# INV_OG5K_PW_V1.net
KiCad netlist of a schematic drawn in Altium Designer
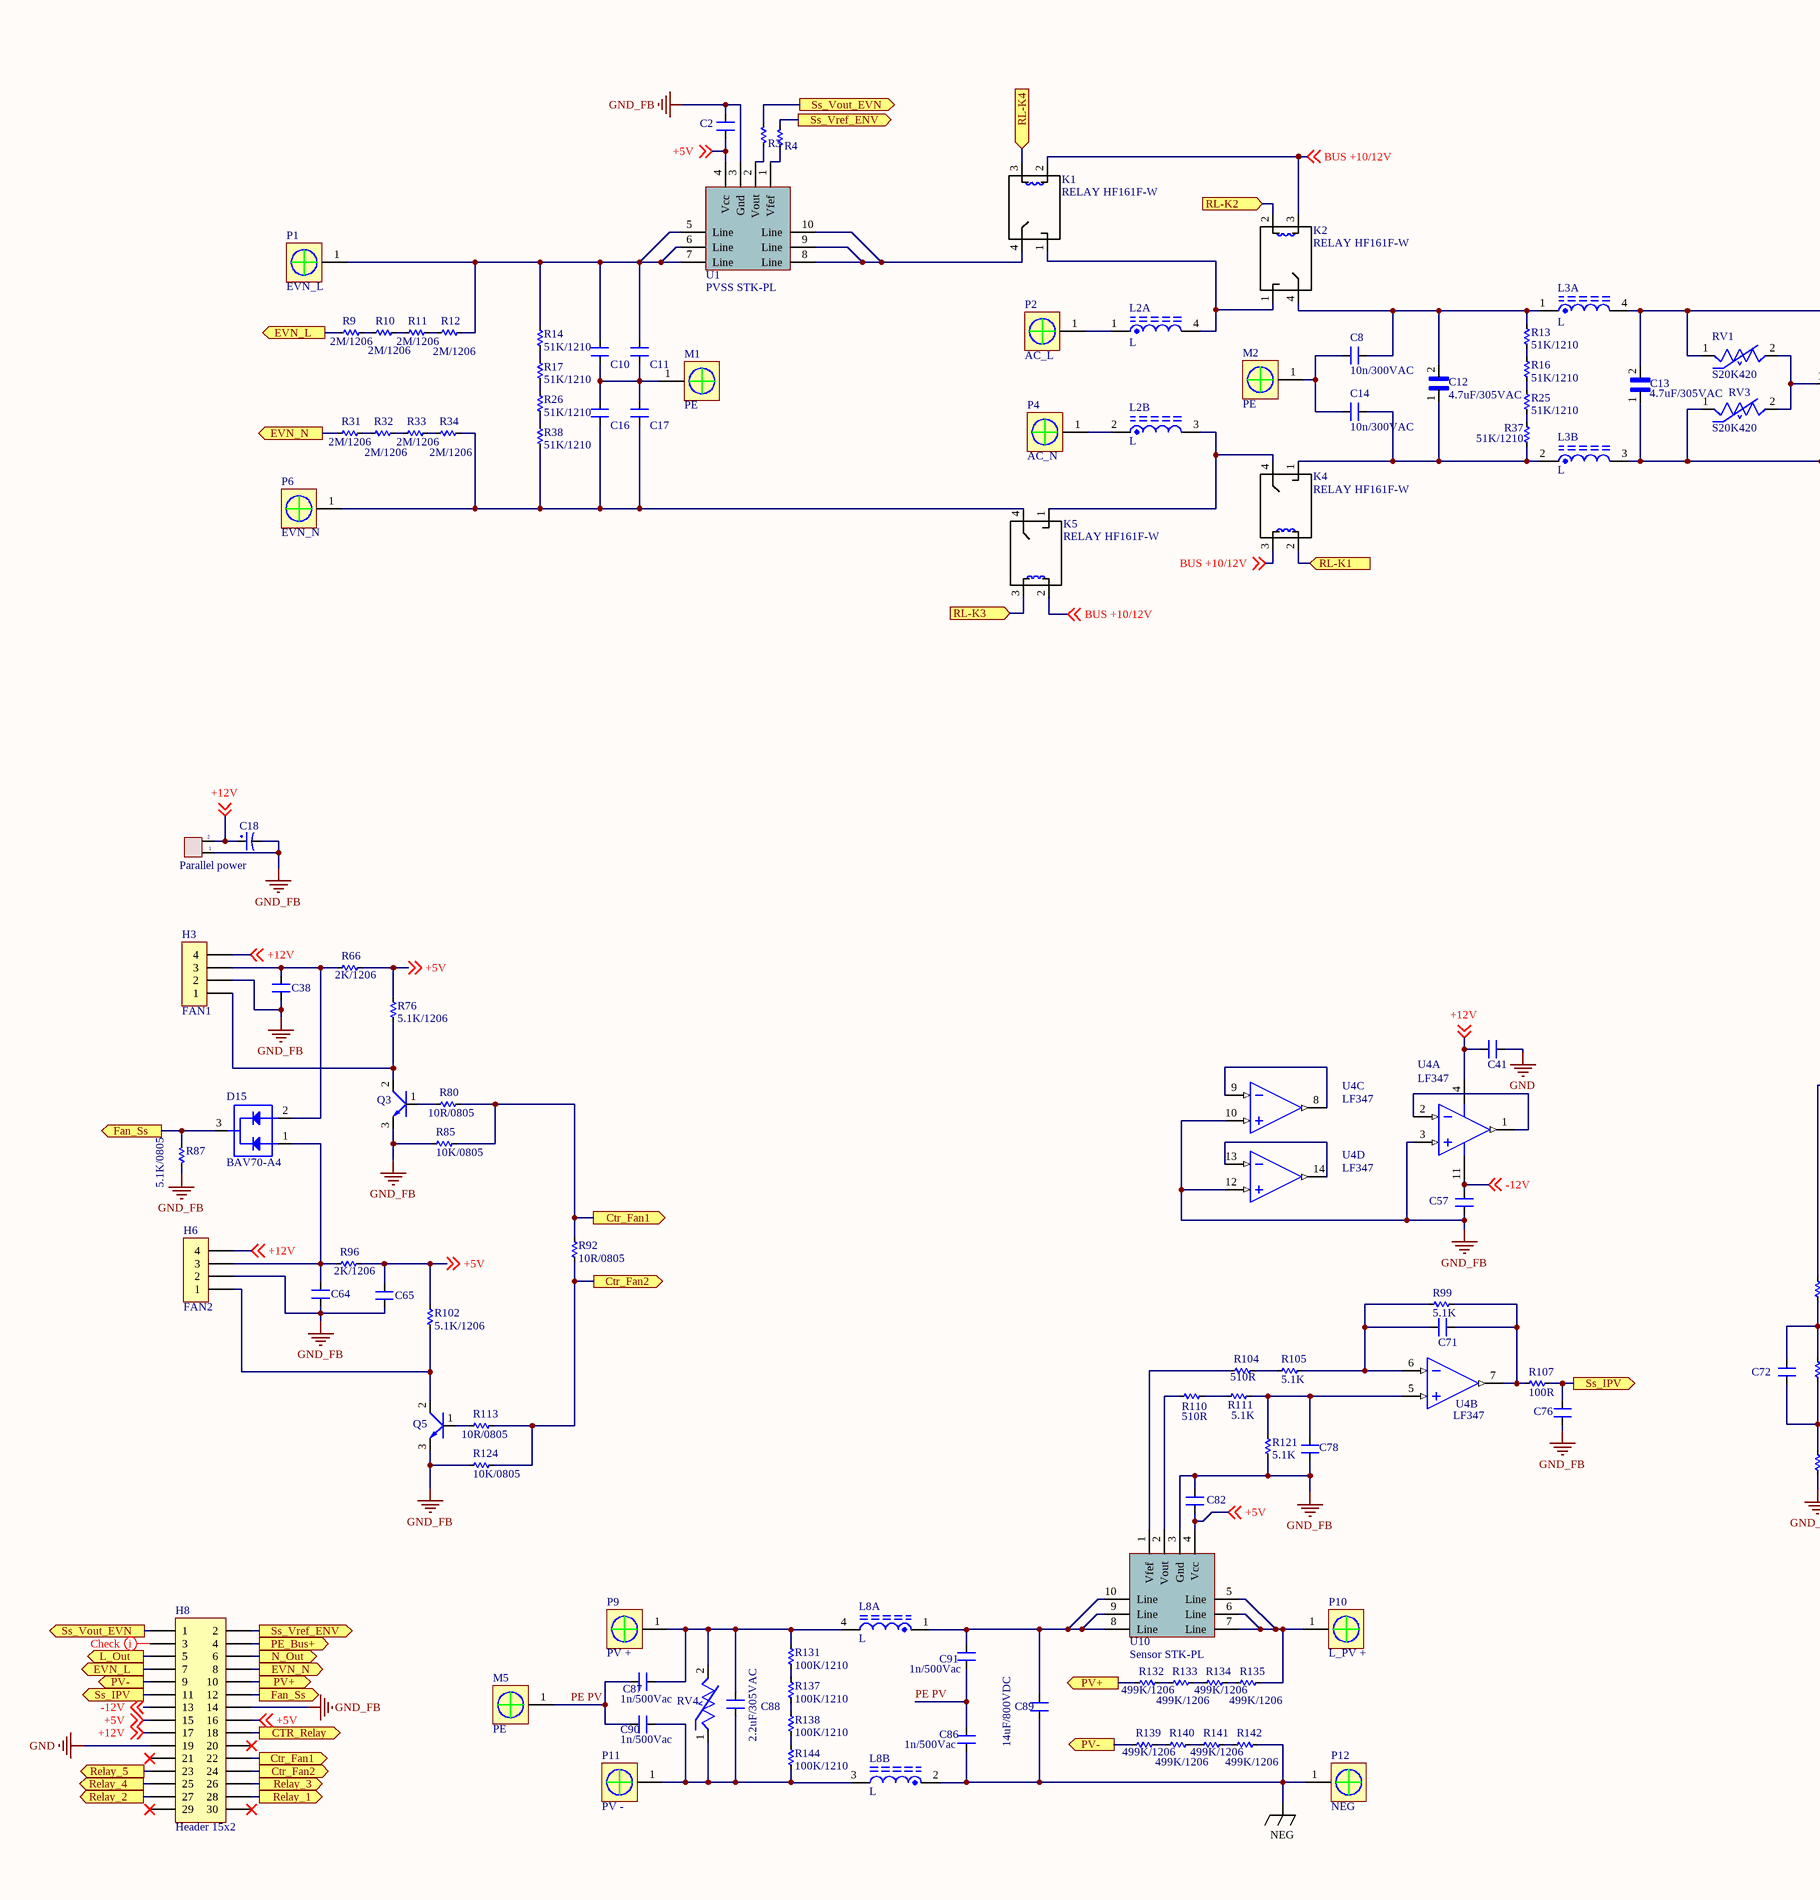
[diagram p0: INV.OG5K.PW.V1.SchDoc, left]
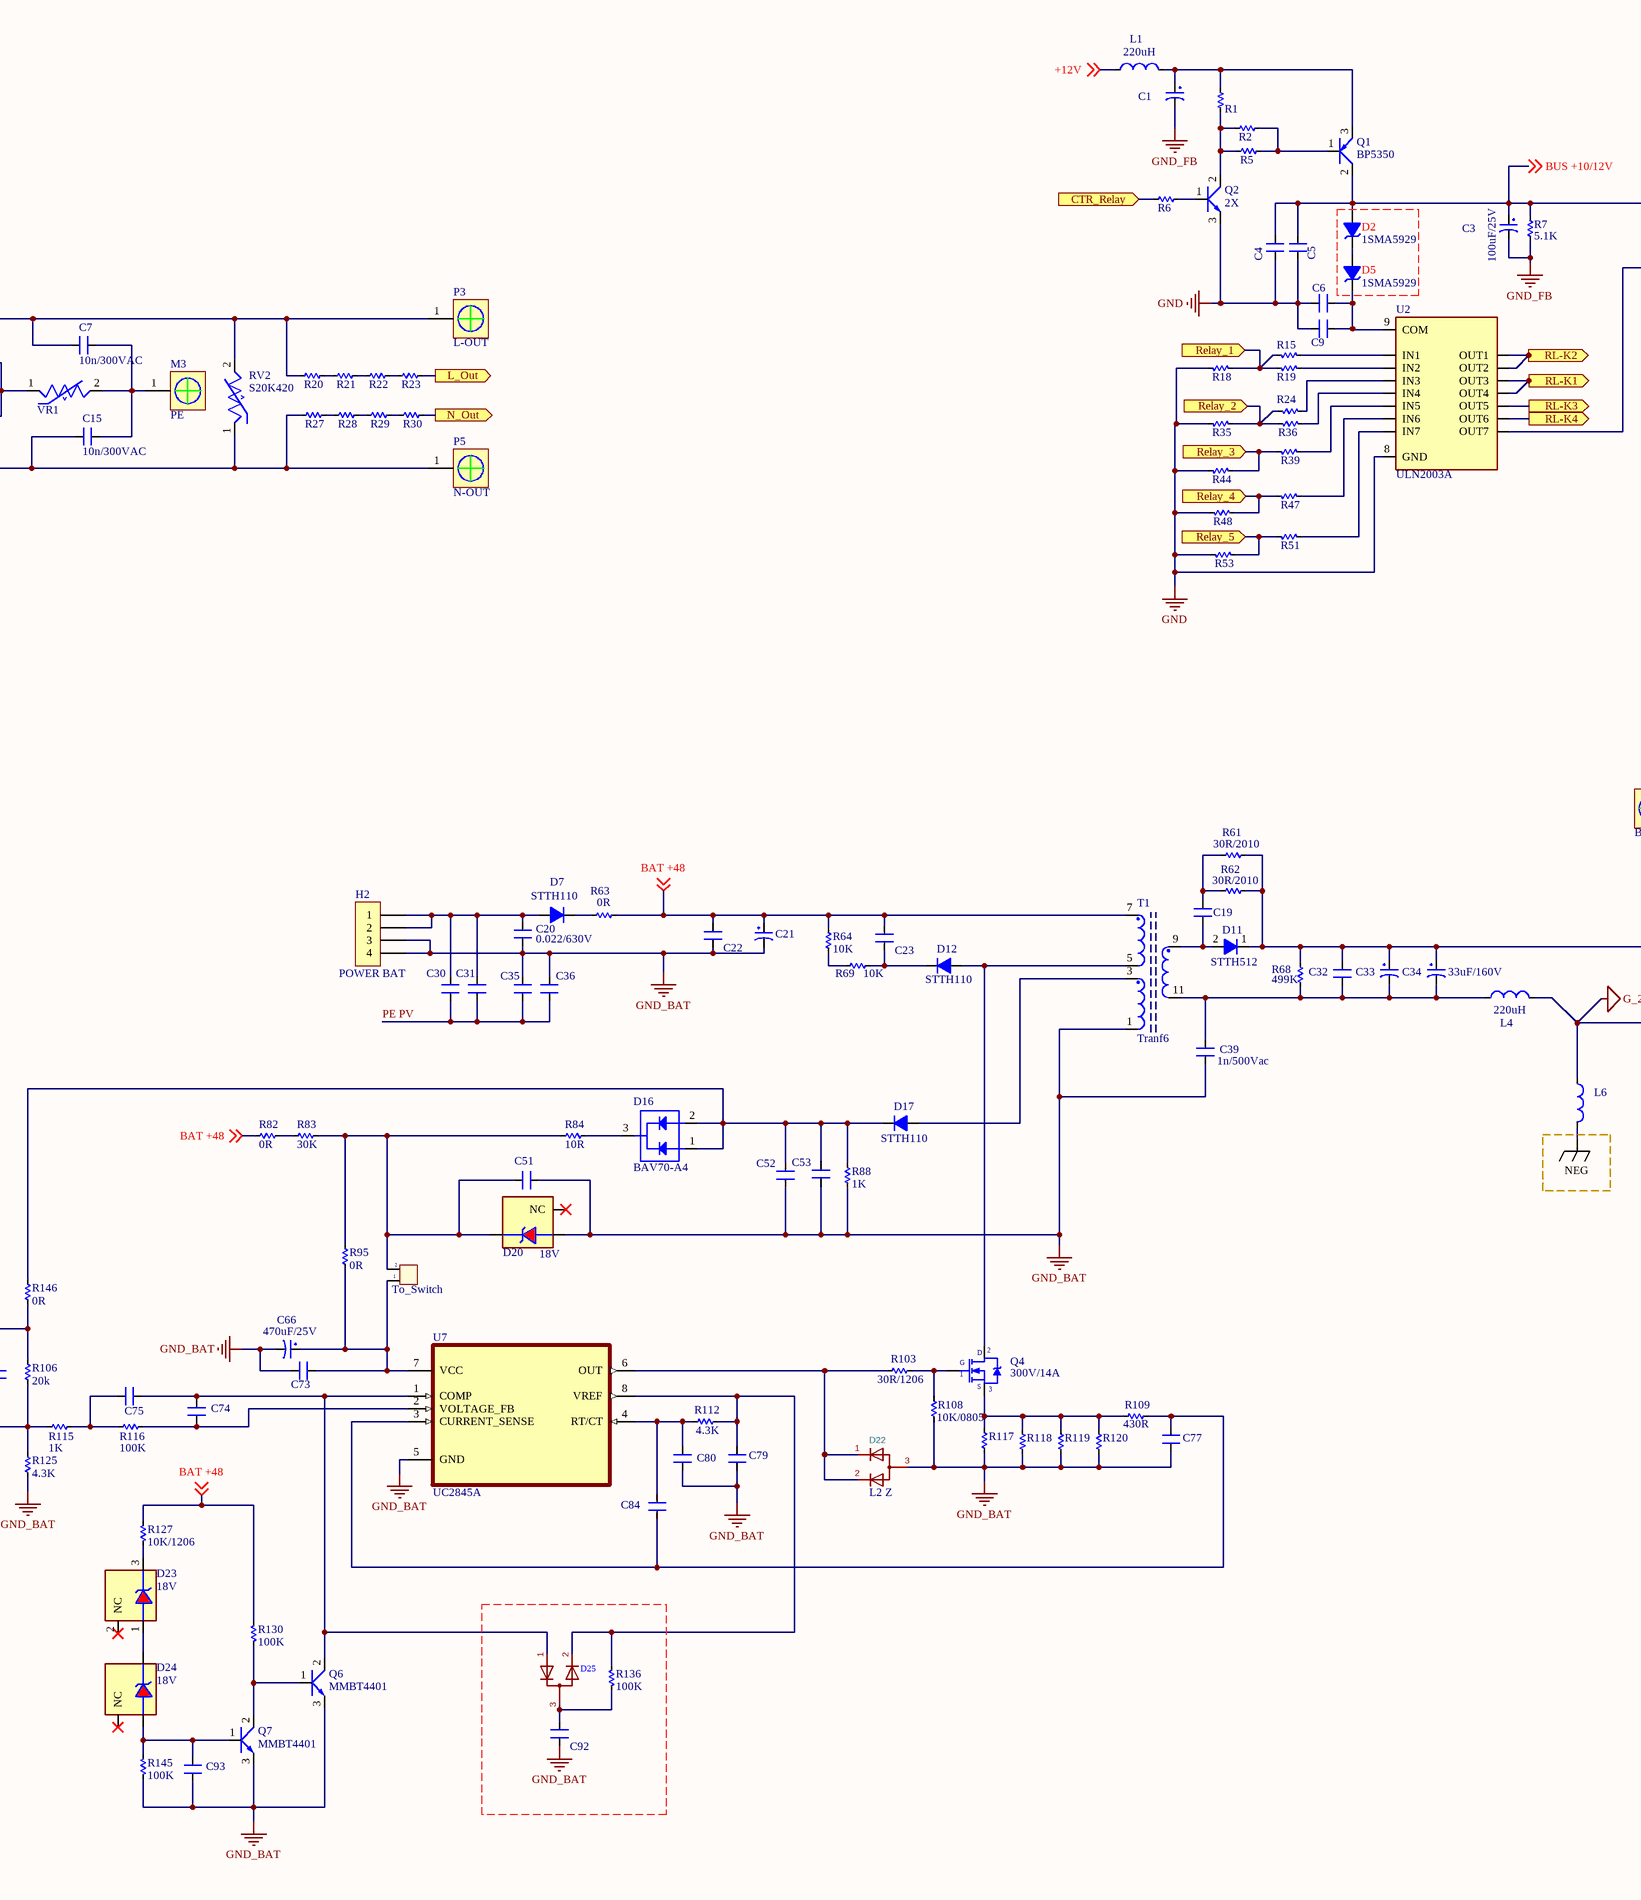
[diagram p1: INV.OG5K.PW.V1.SchDoc, middle]
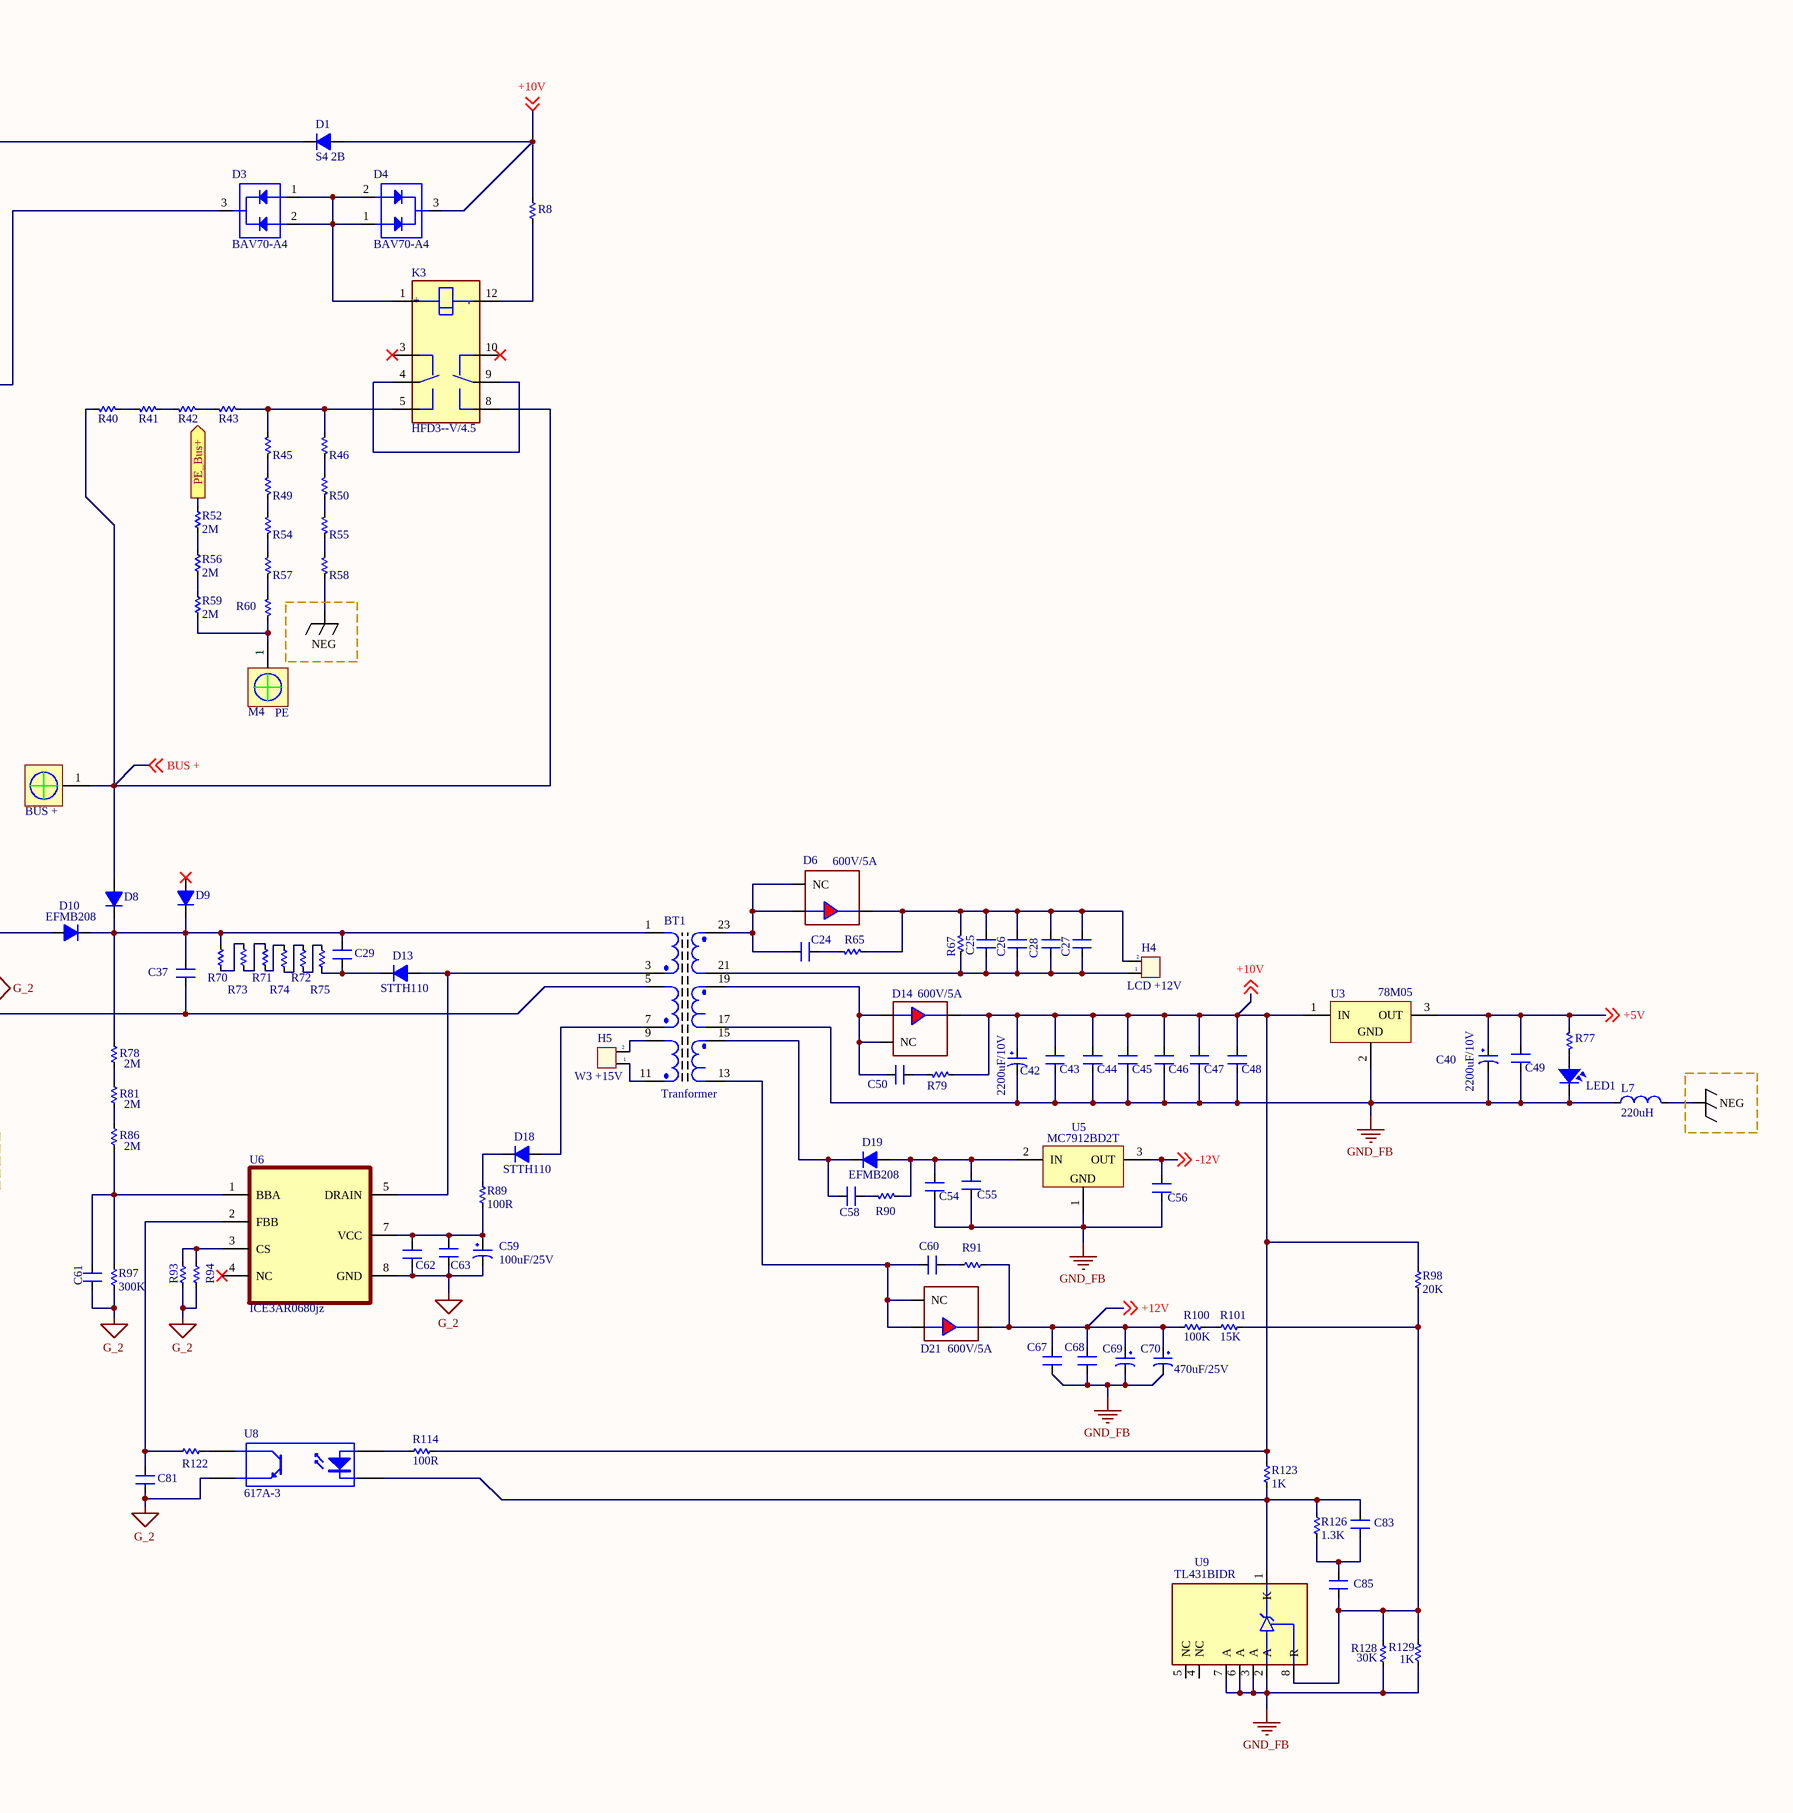
[diagram p2: INV.OG5K.PW.V1.SchDoc, right]

(export (version "E")
  (design (tool "Eeschema 10.0.6"))
  (components
    (comp (ref "BT1")
      (value "Tranformer")
      (footprint "Tranfomer 2-4")
      (description "Bien ap xung DVD")
      (fields (field (name "DESIGNED BY") "VanDungEvn"))
      (libsource (lib "Lib_RD_Cg") (part "Tranfomer 2-4"))
    )
    (comp (ref "C1")
      (value "100uF/25V")
      (footprint "CAP-TH_BD6.3-P2.50-D0.6-FD")
      (libsource (lib "") (part "Cap - 10x18 - N_2"))
    )
    (comp (ref "C2")
      (value "10n/300VAC")
      (footprint "CAP-SMD-0805 EX")
      (description "High Voltage Ceramic Capacitors CS103M")
      (libsource (lib "RAL") (part "CAP-SMD"))
    )
    (comp (ref "C3")
      (value "100uF/25V")
      (footprint "CAP-TH_BD6.3-P2.50-D0.6-FD")
      (libsource (lib "") (part "Cap - 10x18 - N_2"))
    )
    (comp (ref "C4") (value "~") (footprint "CAP-SMD-0805") (libsource (lib "RAL") (part "CAP-SMD")))
    (comp (ref "C5") (value "~") (footprint "CAP-SMD-0805") (libsource (lib "RAL") (part "CAP-SMD")))
    (comp (ref "C6") (value "~") (footprint "CAP-SMD-0805") (libsource (lib "RAL") (part "CAP-SMD")))
    (comp (ref "C7")
      (value "10n/300VAC")
      (footprint "Cap an toan CS103M")
      (description "High Voltage Ceramic Capacitors CS103M")
      (libsource (lib "RAL") (part "CAP-SMD"))
    )
    (comp (ref "C8")
      (value "10n/300VAC")
      (footprint "Cap an toan CS103M")
      (description "High Voltage Ceramic Capacitors CS103M")
      (libsource (lib "RAL") (part "CAP-SMD"))
    )
    (comp (ref "C9") (value "~") (footprint "CAP-SMD-0805") (libsource (lib "RAL") (part "CAP-SMD")))
    (comp (ref "C10")
      (value "10n/300VAC")
      (footprint "Cap an toan CS103M")
      (description "High Voltage Ceramic Capacitors CS103M")
      (libsource (lib "RAL") (part "CAP-SMD"))
    )
    (comp (ref "C11")
      (value "10n/300VAC")
      (footprint "Cap an toan CS103M")
      (description "High Voltage Ceramic Capacitors CS103M")
      (libsource (lib "RAL") (part "CAP-SMD"))
    )
    (comp (ref "C12")
      (value "4.7uF/305VAC")
      (footprint "CAP-TH_L31.5-W21.0-P27.50-D1.0")
      (description "Polypropylene Film Capacitor, 305V ac, ±20%, 4.7μF")
      (fields (field (name "MP") "ECWFG2J475KA") (field (name "MF") "Panasonic"))
      (libsource (lib "Lib_RD_Cg") (part "ECWFG2J475KA"))
    )
    (comp (ref "C13")
      (value "4.7uF/305VAC")
      (footprint "CAP-TH_L31.5-W21.0-P27.50-D1.0")
      (description "Polypropylene Film Capacitor, 305V ac, ±20%, 4.7μF")
      (fields (field (name "MP") "ECWFG2J475KA") (field (name "MF") "Panasonic"))
      (libsource (lib "Lib_RD_Cg") (part "ECWFG2J475KA"))
    )
    (comp (ref "C14")
      (value "10n/300VAC")
      (footprint "Cap an toan CS103M")
      (description "High Voltage Ceramic Capacitors CS103M")
      (libsource (lib "RAL") (part "CAP-SMD"))
    )
    (comp (ref "C15")
      (value "10n/300VAC")
      (footprint "Cap an toan CS103M")
      (description "High Voltage Ceramic Capacitors CS103M")
      (libsource (lib "RAL") (part "CAP-SMD"))
    )
    (comp (ref "C16")
      (value "10n/300VAC")
      (footprint "Cap an toan CS103M")
      (description "High Voltage Ceramic Capacitors CS103M")
      (libsource (lib "RAL") (part "CAP-SMD"))
    )
    (comp (ref "C17")
      (value "10n/300VAC")
      (footprint "Cap an toan CS103M")
      (description "High Voltage Ceramic Capacitors CS103M")
      (libsource (lib "RAL") (part "CAP-SMD"))
    )
    (comp (ref "C18")
      (value "470uF/25V")
      (footprint "CAP-TH_BD8.0-P3.50-D0.6-FD")
      (libsource (lib "") (part "Cap - 10x18 - N_3"))
    )
    (comp (ref "C19") (value "~") (footprint "CAP-SMD-1206") (libsource (lib "RAL") (part "CAP-SMD")))
    (comp (ref "C20")
      (value "0.022/630V")
      (footprint "CAP-TH_L10.5-W5.0-P7.50-D1.2")
      (description "WIMA MKS 4 Metallized Polyester (PET) Capacitors")
      (libsource (lib "RAL") (part "CAP-SMD"))
    )
    (comp (ref "C21")
      (value "27uF/100V")
      (footprint "CAP-TH_BD8.0-P3.50-D0.6-FD")
      (description "Cắm 100uF 25V")
      (libsource (lib "Lib_RD_Cg") (part "Cap - 10x18 - N"))
    )
    (comp (ref "C22") (value "~") (footprint "CAP-SMD-1206") (libsource (lib "RAL") (part "CAP-SMD")))
    (comp (ref "C23") (value "~") (footprint "CAP-SMD-1206") (libsource (lib "RAL") (part "CAP-SMD")))
    (comp (ref "C24") (value "~") (footprint "CAP-SMD-1206") (libsource (lib "RAL") (part "CAP-SMD")))
    (comp (ref "C25") (value "223J630V") (footprint "CAP-SMD-0805") (libsource (lib "RAL") (part "CAP-SMD")))
    (comp (ref "C26") (value "223J630V") (footprint "CAP-SMD-0805") (libsource (lib "RAL") (part "CAP-SMD")))
    (comp (ref "C27") (value "223J630V") (footprint "CAP-SMD-0805") (libsource (lib "RAL") (part "CAP-SMD")))
    (comp (ref "C28") (value "223J630V") (footprint "CAP-SMD-0805") (libsource (lib "RAL") (part "CAP-SMD")))
    (comp (ref "C29")
      (value "223J630V")
      (footprint "CAP-TH_L10.5-W5.0-P7.50-D1.2")
      (libsource (lib "RAL") (part "CAP-SMD"))
    )
    (comp (ref "C30")
      (value "~")
      (footprint "CAP-TH_L10.5-W5.0-P7.50-D1.2")
      (libsource (lib "RAL") (part "CAP-SMD"))
    )
    (comp (ref "C31")
      (value "~")
      (footprint "CAP-TH_L10.5-W5.0-P7.50-D1.2")
      (libsource (lib "RAL") (part "CAP-SMD"))
    )
    (comp (ref "C32") (value "~") (footprint "CAP-SMD-1206") (libsource (lib "RAL") (part "CAP-SMD")))
    (comp (ref "C33")
      (value "33uF/160V")
      (footprint "CAP-TH_BD13.0-P5.00-D0.6-FD")
      (libsource (lib "Lib_RD_Cg") (part "Cap - 10x18 - N"))
    )
    (comp (ref "C34")
      (value "33uF/160V")
      (footprint "CAP-TH_BD13.0-P5.00-D0.6-FD")
      (libsource (lib "Lib_RD_Cg") (part "Cap - 10x18 - N"))
    )
    (comp (ref "C35")
      (value "~")
      (footprint "CAP-TH_L10.5-W5.0-P7.50-D1.2")
      (libsource (lib "RAL") (part "CAP-SMD"))
    )
    (comp (ref "C36")
      (value "~")
      (footprint "CAP-TH_L10.5-W5.0-P7.50-D1.2")
      (libsource (lib "RAL") (part "CAP-SMD"))
    )
    (comp (ref "C37")
      (value "2uF/600VDC")
      (footprint "CAP DIP 31x12")
      (libsource (lib "RAL") (part "CAP-SMD"))
    )
    (comp (ref "C38") (value "~") (footprint "CAP-SMD-0805") (libsource (lib "RAL") (part "CAP-SMD")))
    (comp (ref "C39")
      (value "1n/500Vac")
      (footprint "CAP 1nF/500VAC, Y1")
      (libsource (lib "RAL") (part "CAP-SMD"))
    )
    (comp (ref "C40")
      (value "2200uF/10V")
      (footprint "CAP-TH_BD13.0-P5.00-D0.6-FD")
      (libsource (lib "Lib_RD_Cg") (part "Cap - 10x18 - N"))
    )
    (comp (ref "C41") (value "~") (footprint "CAP-SMD-0805") (libsource (lib "RAL") (part "CAP-SMD")))
    (comp (ref "C42")
      (value "2200uF/10V")
      (footprint "CAP-TH_BD13.0-P5.00-D0.6-FD")
      (libsource (lib "Lib_RD_Cg") (part "Cap - 10x18 - N"))
    )
    (comp (ref "C43") (value "~") (footprint "CAP-SMD-0805") (libsource (lib "RAL") (part "CAP-SMD")))
    (comp (ref "C44") (value "~") (footprint "CAP-SMD-0805") (libsource (lib "RAL") (part "CAP-SMD")))
    (comp (ref "C45") (value "~") (footprint "CAP-SMD-0805") (libsource (lib "RAL") (part "CAP-SMD")))
    (comp (ref "C46") (value "~") (footprint "CAP-SMD-0805") (libsource (lib "RAL") (part "CAP-SMD")))
    (comp (ref "C47") (value "~") (footprint "CAP-SMD-0805") (libsource (lib "RAL") (part "CAP-SMD")))
    (comp (ref "C48") (value "~") (footprint "CAP-SMD-0805") (libsource (lib "RAL") (part "CAP-SMD")))
    (comp (ref "C49") (value "~") (footprint "CAP-SMD-0805") (libsource (lib "RAL") (part "CAP-SMD")))
    (comp (ref "C50") (value "~") (footprint "CAP-SMD-1206") (libsource (lib "RAL") (part "CAP-SMD")))
    (comp (ref "C51") (value "~") (footprint "CAP-SMD-0805") (libsource (lib "RAL") (part "CAP-SMD")))
    (comp (ref "C52") (value "~") (footprint "CAP-SMD-0805") (libsource (lib "RAL") (part "CAP-SMD")))
    (comp (ref "C53") (value "~") (footprint "CAP-SMD-0805") (libsource (lib "RAL") (part "CAP-SMD")))
    (comp (ref "C54") (value "~") (footprint "CAP-SMD-0805") (libsource (lib "RAL") (part "CAP-SMD")))
    (comp (ref "C55") (value "~") (footprint "CAP-SMD-0805") (libsource (lib "RAL") (part "CAP-SMD")))
    (comp (ref "C56") (value "~") (footprint "CAP-SMD-0805") (libsource (lib "RAL") (part "CAP-SMD")))
    (comp (ref "C57") (value "~") (footprint "CAP-SMD-0805") (libsource (lib "RAL") (part "CAP-SMD")))
    (comp (ref "C58") (value "~") (footprint "CAP-SMD-1206") (libsource (lib "RAL") (part "CAP-SMD")))
    (comp (ref "C59")
      (value "100uF/25V")
      (footprint "CAP-TH_BD6.3-P2.50-D0.6-FD")
      (description "Cắm 100uF 25V")
      (libsource (lib "Lib_RD_Cg") (part "Cap - 10x18 - N"))
    )
    (comp (ref "C60") (value "~") (footprint "CAP-SMD-1206") (libsource (lib "RAL") (part "CAP-SMD")))
    (comp (ref "C61") (value "~") (footprint "CAP-SMD-0805") (libsource (lib "RAL") (part "CAP-SMD")))
    (comp (ref "C62") (value "223J630V") (footprint "CAP-SMD-0805") (libsource (lib "RAL") (part "CAP-SMD")))
    (comp (ref "C63") (value "223J630V") (footprint "CAP-SMD-0805") (libsource (lib "RAL") (part "CAP-SMD")))
    (comp (ref "C64") (value "~") (footprint "CAP-SMD-0805") (libsource (lib "RAL") (part "CAP-SMD")))
    (comp (ref "C65") (value "~") (footprint "CAP-SMD-0805") (libsource (lib "RAL") (part "CAP-SMD")))
    (comp (ref "C66")
      (value "470uF/25V")
      (footprint "CAP-TH_BD8.0-P3.50-D0.6-FD")
      (description "Cắm 100uF 25V")
      (libsource (lib "") (part "Cap - 10x18 - N_1"))
    )
    (comp (ref "C67") (value "~") (footprint "CAP-SMD-0805") (libsource (lib "RAL") (part "CAP-SMD")))
    (comp (ref "C68") (value "~") (footprint "CAP-SMD-0805") (libsource (lib "RAL") (part "CAP-SMD")))
    (comp (ref "C69")
      (value "470uF/25V")
      (footprint "CAP-TH_BD8.0-P3.50-D0.6-FD")
      (libsource (lib "") (part "Cap - 10x18 - N_2"))
    )
    (comp (ref "C70")
      (value "470uF/25V")
      (footprint "CAP-TH_BD8.0-P3.50-D0.6-FD")
      (libsource (lib "") (part "Cap - 10x18 - N_2"))
    )
    (comp (ref "C71") (value "~") (footprint "CAP-SMD-0805") (libsource (lib "RAL") (part "CAP-SMD")))
    (comp (ref "C72") (value "~") (footprint "CAP-SMD-0805") (libsource (lib "RAL") (part "CAP-SMD")))
    (comp (ref "C73") (value "~") (footprint "CAP-SMD-0805") (libsource (lib "RAL") (part "CAP-SMD")))
    (comp (ref "C74") (value "~") (footprint "CAP-SMD-0805") (libsource (lib "RAL") (part "CAP-SMD")))
    (comp (ref "C75") (value "~") (footprint "CAP-SMD-0805") (libsource (lib "RAL") (part "CAP-SMD")))
    (comp (ref "C76") (value "~") (footprint "CAP-SMD-0805") (libsource (lib "RAL") (part "CAP-SMD")))
    (comp (ref "C77") (value "~") (footprint "CAP-SMD-0805") (libsource (lib "RAL") (part "CAP-SMD")))
    (comp (ref "C78") (value "~") (footprint "CAP-SMD-0805") (libsource (lib "RAL") (part "CAP-SMD")))
    (comp (ref "C79") (value "~") (footprint "CAP-SMD-0805") (libsource (lib "RAL") (part "CAP-SMD")))
    (comp (ref "C80") (value "~") (footprint "CAP-SMD-0805") (libsource (lib "RAL") (part "CAP-SMD")))
    (comp (ref "C81") (value "~") (footprint "CAP-SMD-0805") (libsource (lib "RAL") (part "CAP-SMD")))
    (comp (ref "C82") (value "~") (footprint "CAP-SMD-0805 EX") (libsource (lib "RAL") (part "CAP-SMD")))
    (comp (ref "C83") (value "~") (footprint "CAP-SMD-0805") (libsource (lib "RAL") (part "CAP-SMD")))
    (comp (ref "C84") (value "~") (footprint "CAP-SMD-0805") (libsource (lib "RAL") (part "CAP-SMD")))
    (comp (ref "C85") (value "~") (footprint "CAP-SMD-0805") (libsource (lib "RAL") (part "CAP-SMD")))
    (comp (ref "C86")
      (value "1n/500Vac")
      (footprint "CAP 1nF/500VAC, Y1")
      (libsource (lib "RAL") (part "CAP-SMD"))
    )
    (comp (ref "C87")
      (value "1n/500Vac")
      (footprint "CAP 1nF/500VAC, Y1")
      (libsource (lib "RAL") (part "CAP-SMD"))
    )
    (comp (ref "C88")
      (value "2.2uF/305VAC")
      (footprint "CAP-TH_L26.5-W14.5-P22.50-D1.2")
      (libsource (lib "RAL") (part "CAP-SMD"))
    )
    (comp (ref "C89")
      (value "14uF/800VDC")
      (footprint "CAP DIP 42x18")
      (libsource (lib "RAL") (part "CAP-SMD"))
    )
    (comp (ref "C90")
      (value "1n/500Vac")
      (footprint "CAP 1nF/500VAC, Y1")
      (libsource (lib "RAL") (part "CAP-SMD"))
    )
    (comp (ref "C91")
      (value "1n/500Vac")
      (footprint "CAP 1nF/500VAC, Y1")
      (libsource (lib "RAL") (part "CAP-SMD"))
    )
    (comp (ref "C92") (value "~") (footprint "CAP-SMD-0805") (libsource (lib "RAL") (part "CAP-SMD")))
    (comp (ref "C93") (value "~") (footprint "CAP-SMD-0805") (libsource (lib "RAL") (part "CAP-SMD")))
    (comp (ref "D1") (value "S4 2B") (footprint "SMB") (libsource (lib "Lib_RD_Cg") (part "DIODE")))
    (comp (ref "D2")
      (value "1SMA5929")
      (footprint "SMA")
      (description "Diode Zenner 15V")
      (libsource (lib "Lib_RD_Cg") (part "DIODE ZENNER"))
    )
    (comp (ref "D3")
      (value "BAV70-A4")
      (footprint "SOT23-132")
      (fields (field (name "MP") "STTH2003CG-TR"))
      (libsource (lib "Lib_RD_Cg") (part "Diode Double"))
    )
    (comp (ref "D4")
      (value "BAV70-A4")
      (footprint "SOT23-132")
      (fields (field (name "MP") "STTH2003CG-TR"))
      (libsource (lib "Lib_RD_Cg") (part "Diode Double"))
    )
    (comp (ref "D5")
      (value "1SMA5929")
      (footprint "SMA")
      (description "Diode Zenner 15V")
      (libsource (lib "Lib_RD_Cg") (part "DIODE ZENNER"))
    )
    (comp (ref "D6")
      (value "600V/5A")
      (footprint "TO252-132")
      (description "600V/5A Diode SHHT 506B")
      (fields (field (name "MF") "ON Semiconductor") (field (name "MP") "BZX84-C7V5"))
      (libsource (lib "Lib_RD_Cg") (part "Diode SHHT 506B"))
    )
    (comp (ref "D7")
      (value "STTH110")
      (footprint "SMA")
      (description "Diode 1000V/1A SMB")
      (libsource (lib "Lib_RD_Cg") (part "DIODE"))
    )
    (comp (ref "D8")
      (value "EFMB208")
      (footprint "SMB")
      (description "Diode 600V/2A SMB thay the ES2J")
      (libsource (lib "Lib_RD_Cg") (part "DIODE"))
    )
    (comp (ref "D9")
      (value "EFMB208")
      (footprint "SMB")
      (description "Diode 600V/2A SMB thay the ES2J")
      (libsource (lib "Lib_RD_Cg") (part "DIODE"))
    )
    (comp (ref "D10")
      (value "EFMB208")
      (footprint "SMB")
      (description "Diode 600V/2A SMB thay the ES2J")
      (libsource (lib "Lib_RD_Cg") (part "DIODE"))
    )
    (comp (ref "D11")
      (value "STTH512")
      (footprint "TO220 - DIP 2 Pin Heatsink")
      (description "Diode 1200V/5A")
      (libsource (lib "") (part "DIODE_1"))
    )
    (comp (ref "D12")
      (value "STTH110")
      (footprint "SMA")
      (description "Diode 1000V/1A SMB")
      (libsource (lib "Lib_RD_Cg") (part "DIODE"))
    )
    (comp (ref "D13")
      (value "STTH110")
      (footprint "SMA")
      (description "Diode 1000V/1A SMB")
      (libsource (lib "Lib_RD_Cg") (part "DIODE"))
    )
    (comp (ref "D14")
      (value "600V/5A")
      (footprint "TO252-132")
      (description "600V/5A Diode SHHT 506B")
      (fields (field (name "MF") "ON Semiconductor") (field (name "MP") "BZX84-C7V5"))
      (libsource (lib "") (part "Diode SHHT 506B_1"))
    )
    (comp (ref "D15")
      (value "BAV70-A4")
      (footprint "SOT23-132")
      (fields (field (name "MP") "STTH2003CG-TR"))
      (libsource (lib "Lib_RD_Cg") (part "Diode Double"))
    )
    (comp (ref "D16")
      (value "BAV70-A4")
      (footprint "SOT23-132")
      (fields (field (name "MP") "STTH2003CG-TR"))
      (libsource (lib "Lib_RD_Cg") (part "Diode Double"))
    )
    (comp (ref "D17")
      (value "STTH110")
      (footprint "SMA")
      (description "Diode 1000V/1A SMB")
      (libsource (lib "Lib_RD_Cg") (part "DIODE"))
    )
    (comp (ref "D18")
      (value "STTH110")
      (footprint "SMB")
      (description "Diode 1000V/1A SMB")
      (libsource (lib "Lib_RD_Cg") (part "DIODE"))
    )
    (comp (ref "D19")
      (value "EFMB208")
      (footprint "SMB")
      (description "Diode 600V/2A SMB thay the ES2J")
      (libsource (lib "Lib_RD_Cg") (part "DIODE"))
    )
    (comp (ref "D20")
      (value "18V")
      (footprint "SOT23-132")
      (description "BZX84-C18(Y6W) Zenner 18V thay the BZT52C18")
      (fields (field (name "MF") "ON Semiconductor") (field (name "MP") "BZX84-C7V5"))
      (libsource (lib "") (part "Diode Zener Sot-95_2"))
    )
    (comp (ref "D21")
      (value "600V/5A")
      (footprint "TO252-132")
      (description "600V/5A Diode SHHT 506B")
      (fields (field (name "MF") "ON Semiconductor") (field (name "MP") "BZX84-C7V5"))
      (libsource (lib "Lib_RD_Cg") (part "Diode SHHT 506B"))
    )
    (comp (ref "D22")
      (value "L2 Z")
      (footprint "SOT23-132")
      (description "LBAS40-06LT1G\r\n S-LBAS40-06LT1G - thay thế BAW56")
      (libsource (lib "Lib_RD_Cg") (part "Dual-Diode_CA"))
    )
    (comp (ref "D23")
      (value "18V")
      (footprint "SOT23-132")
      (description "BZX84-C18(Y6W) Zenner 18V thay the BZT52C18")
      (fields (field (name "MF") "ON Semiconductor") (field (name "MP") "BZX84-C7V5"))
      (libsource (lib "") (part "Diode Zener Sot-95_1"))
    )
    (comp (ref "D24")
      (value "18V")
      (footprint "SOT23-132")
      (description "BZX84-C18(Y6W) Zenner 18V thay the BZT52C18")
      (fields (field (name "MF") "ON Semiconductor") (field (name "MP") "BZX84-C7V5"))
      (libsource (lib "Lib_RD_Cg") (part "Diode Zener Sot-95"))
    )
    (comp (ref "D25")
      (value "Dual-Diode_CA_1")
      (footprint "SOT23-132")
      (description "BAT54S(D88) thay the BAV99:A7")
      (libsource (lib "Lib_RD_Cg") (part "Dual-Diode_CA_1"))
    )
    (comp (ref "H1") (value "Parallel power") (footprint "Header2") (libsource (lib "") (part "Jump2_1")))
    (comp (ref "H2")
      (value "POWER BAT")
      (footprint "Header4")
      (description "Cắm")
      (libsource (lib "") (part "Header 4P 2.54 Duc Thang_1"))
    )
    (comp (ref "H3")
      (value "FAN1")
      (footprint "Header4")
      (description "Cắm")
      (libsource (lib "Altium_Lib_by_KhueNguyenCreator") (part "Header 4P 2.54 Duc Thang"))
    )
    (comp (ref "H4") (value "LCD +12V") (footprint "Header2") (libsource (lib "AE_RD") (part "Jump2")))
    (comp (ref "H5") (value "W3 +15V") (footprint "Header2") (libsource (lib "") (part "Jump2_1")))
    (comp (ref "H6")
      (value "FAN2")
      (footprint "Header4")
      (description "Cắm")
      (libsource (lib "Altium_Lib_by_KhueNguyenCreator") (part "Header 4P 2.54 Duc Thang"))
    )
    (comp (ref "H7") (value "To_Switch") (footprint "Header2") (libsource (lib "AE_RD") (part "Jump2")))
    (comp (ref "H8")
      (value "Header 15x2")
      (footprint "Header 2x15 V2")
      (description "Header, 15x2-Pin 2.5mm")
      (fields (field (name "PUBLISHER") "Altium Limited"))
      (libsource (lib "Lib_RD_Cg") (part "Header 15x2"))
    )
    (comp (ref "K1")
      (value "RELAY HF161F-W")
      (footprint "RELAY HF161F-W")
      (description "RELAY HF161F-W 277V/26A")
      (libsource (lib "Lib_RD_Cg") (part "RELAY 10A/250V-SY"))
    )
    (comp (ref "K2")
      (value "RELAY HF161F-W")
      (footprint "RELAY HF161F-W")
      (description "RELAY HF161F-W 277V/26A")
      (libsource (lib "") (part "RELAY 10A/250V-SY_1"))
    )
    (comp (ref "K3")
      (value "HFD3--V/4.5")
      (footprint "RELAY 3/5-1")
      (fields (field (name "MF") "Hongfa") (field (name "MP") "HFD3/012-L2"))
      (libsource (lib "Lib_RD_Cg") (part "HFD3--V/4.5"))
    )
    (comp (ref "K4")
      (value "RELAY HF161F-W")
      (footprint "RELAY HF161F-W")
      (description "RELAY HF161F-W 277V/26A")
      (libsource (lib "") (part "RELAY 10A/250V-SY_1"))
    )
    (comp (ref "K5")
      (value "RELAY HF161F-W")
      (footprint "RELAY HF161F-W")
      (description "RELAY HF161F-W 277V/26A")
      (libsource (lib "") (part "RELAY 10A/250V-SY_1"))
    )
    (comp (ref "L1")
      (value "220uH")
      (footprint "IND-SMD_L10.2-W10.0_MS104R")
      (description "Inductor")
      (libsource (lib "Lib_RD_Cg") (part "L1"))
    )
    (comp (ref "L2")
      (value "L")
      (footprint "LAC2OG5K-V1")
      (description "Cuon cam AC")
      (fields (field (name "DESIGNED BY") "VanDungEvn"))
      (libsource (lib "Lib_RD_Cg") (part "LAC2OG5K-V1"))
    )
    (comp (ref "L3")
      (value "L")
      (footprint "LAC1OG5K-V1")
      (description "Cuon cam AC")
      (fields (field (name "DESIGNED BY") "VanDungEvn"))
      (libsource (lib "") (part "LAC1OG5K-V1_1"))
    )
    (comp (ref "L4")
      (value "220uH")
      (footprint "IND-SMD_L10.2-W10.0_MS104R")
      (description "Inductor")
      (libsource (lib "Lib_RD_Cg") (part "L1"))
    )
    (comp (ref "L6")
      (value "~")
      (footprint "IND-SMD_L10.2-W10.0_MS104R")
      (description "Inductor")
      (libsource (lib "") (part "L1_1"))
    )
    (comp (ref "L7")
      (value "220uH")
      (footprint "IND-SMD_L10.2-W10.0_MS104R")
      (description "Inductor")
      (libsource (lib "Lib_RD_Cg") (part "L1"))
    )
    (comp (ref "L8")
      (value "L")
      (footprint "LPVOG5K-V1")
      (fields (field (name "DESIGNED BY") "VanDungEvn"))
      (libsource (lib "Lib_RD_Cg") (part "LPVOG5K-V1"))
    )
    (comp (ref "LED1") (value "LED") (footprint "LED-0805-Blue") (libsource (lib "RAL") (part "LED1-SMD")))
    (comp (ref "M1") (value "PE") (footprint "COPER") (libsource (lib "Lib_RD_Cg") (part "Copper")))
    (comp (ref "M2") (value "PE") (footprint "COPER") (libsource (lib "") (part "Copper_1")))
    (comp (ref "M3") (value "PE") (footprint "COPER") (libsource (lib "") (part "Copper_2")))
    (comp (ref "M4") (value "PE") (footprint "COPER") (libsource (lib "") (part "Copper_3")))
    (comp (ref "M5") (value "PE") (footprint "COPER") (libsource (lib "") (part "Copper_1")))
    (comp (ref "P1") (value "EVN_L") (footprint "Copper Pipe 4 DIP") (libsource (lib "") (part "Copper_3")))
    (comp (ref "P2") (value "AC_L") (footprint "Copper Pipe 4 DIP") (libsource (lib "") (part "Copper_1")))
    (comp (ref "P3") (value "L-OUT") (footprint "Copper Pipe 4 DIP") (libsource (lib "") (part "Copper_2")))
    (comp (ref "P4") (value "AC_N") (footprint "Copper Pipe 4 DIP") (libsource (lib "") (part "Copper_1")))
    (comp (ref "P5") (value "N-OUT") (footprint "Copper Pipe 4 DIP") (libsource (lib "") (part "Copper_2")))
    (comp (ref "P6") (value "EVN_N") (footprint "Copper Pipe 4 DIP") (libsource (lib "") (part "Copper_3")))
    (comp (ref "P8") (value "BUS +") (footprint "Copper Pipe 4 DIP") (libsource (lib "") (part "Copper_1")))
    (comp (ref "P9") (value "PV +") (footprint "Copper Pipe 4 DIP") (libsource (lib "") (part "Copper_1")))
    (comp (ref "P10")
      (value "L_PV +")
      (footprint "Copper Pipe 4 DIP")
      (libsource (lib "Lib_RD_Cg") (part "Copper"))
    )
    (comp (ref "P11") (value "PV -") (footprint "Copper Pipe 4 DIP") (libsource (lib "") (part "Copper_1")))
    (comp (ref "P12")
      (value "NEG")
      (footprint "Copper Pipe 4 DIP")
      (libsource (lib "Lib_RD_Cg") (part "Copper"))
    )
    (comp (ref "Q1")
      (value "BP5350")
      (footprint "SOT223")
      (description "thay the B772")
      (libsource (lib "Lib_RD_Cg") (part "B772M-PNP"))
    )
    (comp (ref "Q2")
      (value "2X")
      (footprint "SOT23-123")
      (description "thay the MMPT2222 40V/06A")
      (libsource (lib "Lib_RD_Cg") (part "D882M"))
    )
    (comp (ref "Q3") (value "~") (footprint "SOT23-123") (libsource (lib "Lib_RD_Cg") (part "D882M")))
    (comp (ref "Q4")
      (value "300V/14A")
      (footprint "TO263_123")
      (description "14N30")
      (libsource (lib "RAL") (part "MOSFET IRF N"))
    )
    (comp (ref "Q5") (value "~") (footprint "SOT23-123") (libsource (lib "Lib_RD_Cg") (part "D882M")))
    (comp (ref "Q6")
      (value "MMBT4401")
      (footprint "SOT23-123")
      (description "NPN")
      (libsource (lib "Lib_RD_Cg") (part "D882M"))
    )
    (comp (ref "Q7")
      (value "MMBT4401")
      (footprint "SOT23-123")
      (description "NPN")
      (libsource (lib "Lib_RD_Cg") (part "D882M"))
    )
    (comp (ref "R1")
      (value "10K")
      (footprint "RES-SMD-0805")
      (description "Resistor")
      (fields
        (field (name "MANUFACTURER") "Generic Components")
        (field (name "PUBLISHER") "Altium Hobart Technology Centre")
      )
      (libsource (lib "RAL") (part "Res-SMD"))
    )
    (comp (ref "R2")
      (value "2K")
      (footprint "RES-SMD-0805")
      (description "Resistor")
      (fields
        (field (name "MANUFACTURER") "Generic Components")
        (field (name "PUBLISHER") "Altium Hobart Technology Centre")
      )
      (libsource (lib "RAL") (part "Res-SMD"))
    )
    (comp (ref "R3")
      (value "1K/0603")
      (footprint "RES-SMD-0603 EX")
      (description "Resistor")
      (fields
        (field (name "MANUFACTURER") "Generic Components")
        (field (name "PUBLISHER") "Altium Hobart Technology Centre")
      )
      (libsource (lib "RAL") (part "Res-SMD"))
    )
    (comp (ref "R4")
      (value "1K/0603")
      (footprint "RES-SMD-0603 EX")
      (description "Resistor")
      (fields
        (field (name "MANUFACTURER") "Generic Components")
        (field (name "PUBLISHER") "Altium Hobart Technology Centre")
      )
      (libsource (lib "RAL") (part "Res-SMD"))
    )
    (comp (ref "R5")
      (value "2K")
      (footprint "RES-SMD-0805")
      (description "Resistor")
      (fields
        (field (name "MANUFACTURER") "Generic Components")
        (field (name "PUBLISHER") "Altium Hobart Technology Centre")
      )
      (libsource (lib "RAL") (part "Res-SMD"))
    )
    (comp (ref "R6")
      (value "20K")
      (footprint "RES-SMD-0805")
      (description "Resistor")
      (fields
        (field (name "MANUFACTURER") "Generic Components")
        (field (name "PUBLISHER") "Altium Hobart Technology Centre")
      )
      (libsource (lib "RAL") (part "Res-SMD"))
    )
    (comp (ref "R7")
      (value "5.1K")
      (footprint "RES-SMD-0805")
      (description "Resistor")
      (fields
        (field (name "MANUFACTURER") "Generic Components")
        (field (name "PUBLISHER") "Altium Hobart Technology Centre")
      )
      (libsource (lib "RAL") (part "Res-SMD"))
    )
    (comp (ref "R8")
      (value "51R")
      (footprint "RES-SMD-0805")
      (description "Resistor")
      (fields
        (field (name "MANUFACTURER") "Generic Components")
        (field (name "PUBLISHER") "Altium Hobart Technology Centre")
      )
      (libsource (lib "RAL") (part "Res-SMD"))
    )
    (comp (ref "R9")
      (value "2M/1206")
      (footprint "RES-SMD-1206")
      (description "Resistor")
      (fields
        (field (name "MANUFACTURER") "Generic Components")
        (field (name "PUBLISHER") "Altium Hobart Technology Centre")
      )
      (libsource (lib "RAL") (part "Res-SMD"))
    )
    (comp (ref "R10")
      (value "2M/1206")
      (footprint "RES-SMD-1206")
      (description "Resistor")
      (fields
        (field (name "MANUFACTURER") "Generic Components")
        (field (name "PUBLISHER") "Altium Hobart Technology Centre")
      )
      (libsource (lib "RAL") (part "Res-SMD"))
    )
    (comp (ref "R11")
      (value "2M/1206")
      (footprint "RES-SMD-1206")
      (description "Resistor")
      (fields
        (field (name "MANUFACTURER") "Generic Components")
        (field (name "PUBLISHER") "Altium Hobart Technology Centre")
      )
      (libsource (lib "RAL") (part "Res-SMD"))
    )
    (comp (ref "R12")
      (value "2M/1206")
      (footprint "RES-SMD-1206")
      (description "Resistor")
      (fields
        (field (name "MANUFACTURER") "Generic Components")
        (field (name "PUBLISHER") "Altium Hobart Technology Centre")
      )
      (libsource (lib "RAL") (part "Res-SMD"))
    )
    (comp (ref "R13")
      (value "51K/1210")
      (footprint "RES-SMD-1210 EX")
      (description "Resistor")
      (fields
        (field (name "MANUFACTURER") "Generic Components")
        (field (name "PUBLISHER") "Altium Hobart Technology Centre")
      )
      (libsource (lib "RAL") (part "Res-SMD"))
    )
    (comp (ref "R14")
      (value "51K/1210")
      (footprint "RES-SMD-1210 EX")
      (description "Resistor")
      (fields
        (field (name "MANUFACTURER") "Generic Components")
        (field (name "PUBLISHER") "Altium Hobart Technology Centre")
      )
      (libsource (lib "RAL") (part "Res-SMD"))
    )
    (comp (ref "R15")
      (value "10R")
      (footprint "RES-SMD-0805")
      (description "Resistor")
      (fields
        (field (name "MANUFACTURER") "Generic Components")
        (field (name "PUBLISHER") "Altium Hobart Technology Centre")
      )
      (libsource (lib "RAL") (part "Res-SMD"))
    )
    (comp (ref "R16")
      (value "51K/1210")
      (footprint "RES-SMD-1210 EX")
      (description "Resistor")
      (fields
        (field (name "MANUFACTURER") "Generic Components")
        (field (name "PUBLISHER") "Altium Hobart Technology Centre")
      )
      (libsource (lib "RAL") (part "Res-SMD"))
    )
    (comp (ref "R17")
      (value "51K/1210")
      (footprint "RES-SMD-1210 EX")
      (description "Resistor")
      (fields
        (field (name "MANUFACTURER") "Generic Components")
        (field (name "PUBLISHER") "Altium Hobart Technology Centre")
      )
      (libsource (lib "RAL") (part "Res-SMD"))
    )
    (comp (ref "R18")
      (value "5.1K")
      (footprint "RES-SMD-0805")
      (description "Resistor")
      (fields
        (field (name "MANUFACTURER") "Generic Components")
        (field (name "PUBLISHER") "Altium Hobart Technology Centre")
      )
      (libsource (lib "RAL") (part "Res-SMD"))
    )
    (comp (ref "R19")
      (value "10R")
      (footprint "RES-SMD-0805")
      (description "Resistor")
      (fields
        (field (name "MANUFACTURER") "Generic Components")
        (field (name "PUBLISHER") "Altium Hobart Technology Centre")
      )
      (libsource (lib "RAL") (part "Res-SMD"))
    )
    (comp (ref "R20")
      (value "2M/1206")
      (footprint "RES-SMD-1206")
      (description "Resistor")
      (fields
        (field (name "MANUFACTURER") "Generic Components")
        (field (name "PUBLISHER") "Altium Hobart Technology Centre")
      )
      (libsource (lib "RAL") (part "Res-SMD"))
    )
    (comp (ref "R21")
      (value "2M/1206")
      (footprint "RES-SMD-1206")
      (description "Resistor")
      (fields
        (field (name "MANUFACTURER") "Generic Components")
        (field (name "PUBLISHER") "Altium Hobart Technology Centre")
      )
      (libsource (lib "RAL") (part "Res-SMD"))
    )
    (comp (ref "R22")
      (value "2M/1206")
      (footprint "RES-SMD-1206")
      (description "Resistor")
      (fields
        (field (name "MANUFACTURER") "Generic Components")
        (field (name "PUBLISHER") "Altium Hobart Technology Centre")
      )
      (libsource (lib "RAL") (part "Res-SMD"))
    )
    (comp (ref "R23")
      (value "2M/1206")
      (footprint "RES-SMD-1206")
      (description "Resistor")
      (fields
        (field (name "MANUFACTURER") "Generic Components")
        (field (name "PUBLISHER") "Altium Hobart Technology Centre")
      )
      (libsource (lib "RAL") (part "Res-SMD"))
    )
    (comp (ref "R24")
      (value "10R")
      (footprint "RES-SMD-0805")
      (description "Resistor")
      (fields
        (field (name "MANUFACTURER") "Generic Components")
        (field (name "PUBLISHER") "Altium Hobart Technology Centre")
      )
      (libsource (lib "RAL") (part "Res-SMD"))
    )
    (comp (ref "R25")
      (value "51K/1210")
      (footprint "RES-SMD-1210 EX")
      (description "Resistor")
      (fields
        (field (name "MANUFACTURER") "Generic Components")
        (field (name "PUBLISHER") "Altium Hobart Technology Centre")
      )
      (libsource (lib "RAL") (part "Res-SMD"))
    )
    (comp (ref "R26")
      (value "51K/1210")
      (footprint "RES-SMD-1210 EX")
      (description "Resistor")
      (fields
        (field (name "MANUFACTURER") "Generic Components")
        (field (name "PUBLISHER") "Altium Hobart Technology Centre")
      )
      (libsource (lib "RAL") (part "Res-SMD"))
    )
    (comp (ref "R27")
      (value "2M/1206")
      (footprint "RES-SMD-1206")
      (description "Resistor")
      (fields
        (field (name "MANUFACTURER") "Generic Components")
        (field (name "PUBLISHER") "Altium Hobart Technology Centre")
      )
      (libsource (lib "RAL") (part "Res-SMD"))
    )
    (comp (ref "R28")
      (value "2M/1206")
      (footprint "RES-SMD-1206")
      (description "Resistor")
      (fields
        (field (name "MANUFACTURER") "Generic Components")
        (field (name "PUBLISHER") "Altium Hobart Technology Centre")
      )
      (libsource (lib "RAL") (part "Res-SMD"))
    )
    (comp (ref "R29")
      (value "2M/1206")
      (footprint "RES-SMD-1206")
      (description "Resistor")
      (fields
        (field (name "MANUFACTURER") "Generic Components")
        (field (name "PUBLISHER") "Altium Hobart Technology Centre")
      )
      (libsource (lib "RAL") (part "Res-SMD"))
    )
    (comp (ref "R30")
      (value "2M/1206")
      (footprint "RES-SMD-1206")
      (description "Resistor")
      (fields
        (field (name "MANUFACTURER") "Generic Components")
        (field (name "PUBLISHER") "Altium Hobart Technology Centre")
      )
      (libsource (lib "RAL") (part "Res-SMD"))
    )
    (comp (ref "R31")
      (value "2M/1206")
      (footprint "RES-SMD-1206")
      (description "Resistor")
      (fields
        (field (name "MANUFACTURER") "Generic Components")
        (field (name "PUBLISHER") "Altium Hobart Technology Centre")
      )
      (libsource (lib "RAL") (part "Res-SMD"))
    )
    (comp (ref "R32")
      (value "2M/1206")
      (footprint "RES-SMD-1206")
      (description "Resistor")
      (fields
        (field (name "MANUFACTURER") "Generic Components")
        (field (name "PUBLISHER") "Altium Hobart Technology Centre")
      )
      (libsource (lib "RAL") (part "Res-SMD"))
    )
    (comp (ref "R33")
      (value "2M/1206")
      (footprint "RES-SMD-1206")
      (description "Resistor")
      (fields
        (field (name "MANUFACTURER") "Generic Components")
        (field (name "PUBLISHER") "Altium Hobart Technology Centre")
      )
      (libsource (lib "RAL") (part "Res-SMD"))
    )
    (comp (ref "R34")
      (value "2M/1206")
      (footprint "RES-SMD-1206")
      (description "Resistor")
      (fields
        (field (name "MANUFACTURER") "Generic Components")
        (field (name "PUBLISHER") "Altium Hobart Technology Centre")
      )
      (libsource (lib "RAL") (part "Res-SMD"))
    )
    (comp (ref "R35")
      (value "5.1K")
      (footprint "RES-SMD-0805")
      (description "Resistor")
      (fields
        (field (name "MANUFACTURER") "Generic Components")
        (field (name "PUBLISHER") "Altium Hobart Technology Centre")
      )
      (libsource (lib "RAL") (part "Res-SMD"))
    )
    (comp (ref "R36")
      (value "10R")
      (footprint "RES-SMD-0805")
      (description "Resistor")
      (fields
        (field (name "MANUFACTURER") "Generic Components")
        (field (name "PUBLISHER") "Altium Hobart Technology Centre")
      )
      (libsource (lib "RAL") (part "Res-SMD"))
    )
    (comp (ref "R37")
      (value "51K/1210")
      (footprint "RES-SMD-1210 EX")
      (description "Resistor")
      (fields
        (field (name "MANUFACTURER") "Generic Components")
        (field (name "PUBLISHER") "Altium Hobart Technology Centre")
      )
      (libsource (lib "RAL") (part "Res-SMD"))
    )
    (comp (ref "R38")
      (value "51K/1210")
      (footprint "RES-SMD-1210 EX")
      (description "Resistor")
      (fields
        (field (name "MANUFACTURER") "Generic Components")
        (field (name "PUBLISHER") "Altium Hobart Technology Centre")
      )
      (libsource (lib "RAL") (part "Res-SMD"))
    )
    (comp (ref "R39")
      (value "10R")
      (footprint "RES-SMD-0805")
      (description "Resistor")
      (fields
        (field (name "MANUFACTURER") "Generic Components")
        (field (name "PUBLISHER") "Altium Hobart Technology Centre")
      )
      (libsource (lib "RAL") (part "Res-SMD"))
    )
    (comp (ref "R40")
      (value "499K")
      (footprint "RES-SMD-1206")
      (description "Resistor")
      (fields
        (field (name "MANUFACTURER") "Generic Components")
        (field (name "PUBLISHER") "Altium Hobart Technology Centre")
      )
      (libsource (lib "RAL") (part "Res-SMD"))
    )
    (comp (ref "R41")
      (value "499K")
      (footprint "RES-SMD-1206")
      (description "Resistor")
      (fields
        (field (name "MANUFACTURER") "Generic Components")
        (field (name "PUBLISHER") "Altium Hobart Technology Centre")
      )
      (libsource (lib "RAL") (part "Res-SMD"))
    )
    (comp (ref "R42")
      (value "499K")
      (footprint "RES-SMD-1206")
      (description "Resistor")
      (fields
        (field (name "MANUFACTURER") "Generic Components")
        (field (name "PUBLISHER") "Altium Hobart Technology Centre")
      )
      (libsource (lib "RAL") (part "Res-SMD"))
    )
    (comp (ref "R43")
      (value "499K")
      (footprint "RES-SMD-1206")
      (description "Resistor")
      (fields
        (field (name "MANUFACTURER") "Generic Components")
        (field (name "PUBLISHER") "Altium Hobart Technology Centre")
      )
      (libsource (lib "RAL") (part "Res-SMD"))
    )
    (comp (ref "R44")
      (value "5.1K")
      (footprint "RES-SMD-0805")
      (description "Resistor")
      (fields
        (field (name "MANUFACTURER") "Generic Components")
        (field (name "PUBLISHER") "Altium Hobart Technology Centre")
      )
      (libsource (lib "RAL") (part "Res-SMD"))
    )
    (comp (ref "R45")
      (value "200K")
      (footprint "RES-SMD-1206")
      (description "Resistor")
      (fields
        (field (name "MANUFACTURER") "Generic Components")
        (field (name "PUBLISHER") "Altium Hobart Technology Centre")
      )
      (libsource (lib "RAL") (part "Res-SMD"))
    )
    (comp (ref "R46")
      (value "499K")
      (footprint "RES-SMD-1206")
      (description "Resistor")
      (fields
        (field (name "MANUFACTURER") "Generic Components")
        (field (name "PUBLISHER") "Altium Hobart Technology Centre")
      )
      (libsource (lib "RAL") (part "Res-SMD"))
    )
    (comp (ref "R47")
      (value "10R")
      (footprint "RES-SMD-0805")
      (description "Resistor")
      (fields
        (field (name "MANUFACTURER") "Generic Components")
        (field (name "PUBLISHER") "Altium Hobart Technology Centre")
      )
      (libsource (lib "RAL") (part "Res-SMD"))
    )
    (comp (ref "R48")
      (value "5.1K")
      (footprint "RES-SMD-0805")
      (description "Resistor")
      (fields
        (field (name "MANUFACTURER") "Generic Components")
        (field (name "PUBLISHER") "Altium Hobart Technology Centre")
      )
      (libsource (lib "RAL") (part "Res-SMD"))
    )
    (comp (ref "R49")
      (value "200K")
      (footprint "RES-SMD-1206")
      (description "Resistor")
      (fields
        (field (name "MANUFACTURER") "Generic Components")
        (field (name "PUBLISHER") "Altium Hobart Technology Centre")
      )
      (libsource (lib "RAL") (part "Res-SMD"))
    )
    (comp (ref "R50")
      (value "499K")
      (footprint "RES-SMD-1206")
      (description "Resistor")
      (fields
        (field (name "MANUFACTURER") "Generic Components")
        (field (name "PUBLISHER") "Altium Hobart Technology Centre")
      )
      (libsource (lib "RAL") (part "Res-SMD"))
    )
    (comp (ref "R51")
      (value "10R")
      (footprint "RES-SMD-0805")
      (description "Resistor")
      (fields
        (field (name "MANUFACTURER") "Generic Components")
        (field (name "PUBLISHER") "Altium Hobart Technology Centre")
      )
      (libsource (lib "RAL") (part "Res-SMD"))
    )
    (comp (ref "R52")
      (value "2M")
      (footprint "RES-SMD-1206")
      (description "Resistor")
      (fields
        (field (name "MANUFACTURER") "Generic Components")
        (field (name "PUBLISHER") "Altium Hobart Technology Centre")
      )
      (libsource (lib "RAL") (part "Res-SMD"))
    )
    (comp (ref "R53")
      (value "5.1K")
      (footprint "RES-SMD-0805")
      (description "Resistor")
      (fields
        (field (name "MANUFACTURER") "Generic Components")
        (field (name "PUBLISHER") "Altium Hobart Technology Centre")
      )
      (libsource (lib "RAL") (part "Res-SMD"))
    )
    (comp (ref "R54")
      (value "200K")
      (footprint "RES-SMD-1206")
      (description "Resistor")
      (fields
        (field (name "MANUFACTURER") "Generic Components")
        (field (name "PUBLISHER") "Altium Hobart Technology Centre")
      )
      (libsource (lib "RAL") (part "Res-SMD"))
    )
    (comp (ref "R55")
      (value "499K")
      (footprint "RES-SMD-1206")
      (description "Resistor")
      (fields
        (field (name "MANUFACTURER") "Generic Components")
        (field (name "PUBLISHER") "Altium Hobart Technology Centre")
      )
      (libsource (lib "RAL") (part "Res-SMD"))
    )
    (comp (ref "R56")
      (value "2M")
      (footprint "RES-SMD-1206")
      (description "Resistor")
      (fields
        (field (name "MANUFACTURER") "Generic Components")
        (field (name "PUBLISHER") "Altium Hobart Technology Centre")
      )
      (libsource (lib "RAL") (part "Res-SMD"))
    )
    (comp (ref "R57")
      (value "200K")
      (footprint "RES-SMD-1206")
      (description "Resistor")
      (fields
        (field (name "MANUFACTURER") "Generic Components")
        (field (name "PUBLISHER") "Altium Hobart Technology Centre")
      )
      (libsource (lib "RAL") (part "Res-SMD"))
    )
    (comp (ref "R58")
      (value "499K")
      (footprint "RES-SMD-1206")
      (description "Resistor")
      (fields
        (field (name "MANUFACTURER") "Generic Components")
        (field (name "PUBLISHER") "Altium Hobart Technology Centre")
      )
      (libsource (lib "RAL") (part "Res-SMD"))
    )
    (comp (ref "R59")
      (value "2M")
      (footprint "RES-SMD-1206")
      (description "Resistor")
      (fields
        (field (name "MANUFACTURER") "Generic Components")
        (field (name "PUBLISHER") "Altium Hobart Technology Centre")
      )
      (libsource (lib "RAL") (part "Res-SMD"))
    )
    (comp (ref "R60")
      (value "200K")
      (footprint "RES-SMD-1206")
      (description "Resistor")
      (fields
        (field (name "MANUFACTURER") "Generic Components")
        (field (name "PUBLISHER") "Altium Hobart Technology Centre")
      )
      (libsource (lib "RAL") (part "Res-SMD"))
    )
    (comp (ref "R61")
      (value "30R/2010")
      (footprint "RES-SMD-1210")
      (description "Resistor")
      (fields
        (field (name "MANUFACTURER") "Generic Components")
        (field (name "PUBLISHER") "Altium Hobart Technology Centre")
      )
      (libsource (lib "RAL") (part "Res-SMD"))
    )
    (comp (ref "R62")
      (value "30R/2010")
      (footprint "RES-SMD-1210")
      (description "Resistor")
      (fields
        (field (name "MANUFACTURER") "Generic Components")
        (field (name "PUBLISHER") "Altium Hobart Technology Centre")
      )
      (libsource (lib "RAL") (part "Res-SMD"))
    )
    (comp (ref "R63")
      (value "0R")
      (footprint "RES-SMD-1206")
      (description "Resistor")
      (fields
        (field (name "MANUFACTURER") "Generic Components")
        (field (name "PUBLISHER") "Altium Hobart Technology Centre")
      )
      (libsource (lib "RAL") (part "Res-SMD"))
    )
    (comp (ref "R64")
      (value "10K")
      (footprint "RES-SMD-0805")
      (description "Resistor")
      (fields
        (field (name "MANUFACTURER") "Generic Components")
        (field (name "PUBLISHER") "Altium Hobart Technology Centre")
      )
      (libsource (lib "RAL") (part "Res-SMD"))
    )
    (comp (ref "R65")
      (value "10K/2010")
      (footprint "RES-SMD-1206")
      (description "Resistor")
      (fields
        (field (name "MANUFACTURER") "Generic Components")
        (field (name "PUBLISHER") "Altium Hobart Technology Centre")
      )
      (libsource (lib "RAL") (part "Res-SMD"))
    )
    (comp (ref "R66")
      (value "2K/1206")
      (footprint "RES-SMD-1206")
      (description "Resistor")
      (fields
        (field (name "MANUFACTURER") "Generic Components")
        (field (name "PUBLISHER") "Altium Hobart Technology Centre")
      )
      (libsource (lib "RAL") (part "Res-SMD"))
    )
    (comp (ref "R67")
      (value "10K/2010")
      (footprint "RES-SMD-0805")
      (description "Resistor")
      (fields
        (field (name "MANUFACTURER") "Generic Components")
        (field (name "PUBLISHER") "Altium Hobart Technology Centre")
      )
      (libsource (lib "RAL") (part "Res-SMD"))
    )
    (comp (ref "R68")
      (value "499K")
      (footprint "RES-SMD-1206")
      (description "Resistor")
      (fields
        (field (name "MANUFACTURER") "Generic Components")
        (field (name "PUBLISHER") "Altium Hobart Technology Centre")
      )
      (libsource (lib "RAL") (part "Res-SMD"))
    )
    (comp (ref "R69")
      (value "10K")
      (footprint "RES-SMD-0805")
      (description "Resistor")
      (fields
        (field (name "MANUFACTURER") "Generic Components")
        (field (name "PUBLISHER") "Altium Hobart Technology Centre")
      )
      (libsource (lib "RAL") (part "Res-SMD"))
    )
    (comp (ref "R70")
      (value "10K/2010")
      (footprint "RES-SMD-1210")
      (description "Resistor")
      (fields
        (field (name "MANUFACTURER") "Generic Components")
        (field (name "PUBLISHER") "Altium Hobart Technology Centre")
      )
      (libsource (lib "RAL") (part "Res-SMD"))
    )
    (comp (ref "R71")
      (value "10K/2010")
      (footprint "RES-SMD-1210")
      (description "Resistor")
      (fields
        (field (name "MANUFACTURER") "Generic Components")
        (field (name "PUBLISHER") "Altium Hobart Technology Centre")
      )
      (libsource (lib "RAL") (part "Res-SMD"))
    )
    (comp (ref "R72")
      (value "10K/2010")
      (footprint "RES-SMD-1210")
      (description "Resistor")
      (fields
        (field (name "MANUFACTURER") "Generic Components")
        (field (name "PUBLISHER") "Altium Hobart Technology Centre")
      )
      (libsource (lib "RAL") (part "Res-SMD"))
    )
    (comp (ref "R73")
      (value "10K/2010")
      (footprint "RES-SMD-1210")
      (description "Resistor")
      (fields
        (field (name "MANUFACTURER") "Generic Components")
        (field (name "PUBLISHER") "Altium Hobart Technology Centre")
      )
      (libsource (lib "RAL") (part "Res-SMD"))
    )
    (comp (ref "R74")
      (value "10K/2010")
      (footprint "RES-SMD-1210")
      (description "Resistor")
      (fields
        (field (name "MANUFACTURER") "Generic Components")
        (field (name "PUBLISHER") "Altium Hobart Technology Centre")
      )
      (libsource (lib "RAL") (part "Res-SMD"))
    )
    (comp (ref "R75")
      (value "10K/2010")
      (footprint "RES-SMD-1210")
      (description "Resistor")
      (fields
        (field (name "MANUFACTURER") "Generic Components")
        (field (name "PUBLISHER") "Altium Hobart Technology Centre")
      )
      (libsource (lib "RAL") (part "Res-SMD"))
    )
    (comp (ref "R76")
      (value "5.1K/1206")
      (footprint "RES-SMD-1206")
      (description "Resistor")
      (fields
        (field (name "MANUFACTURER") "Generic Components")
        (field (name "PUBLISHER") "Altium Hobart Technology Centre")
      )
      (libsource (lib "RAL") (part "Res-SMD"))
    )
    (comp (ref "R77")
      (value "5.1K")
      (footprint "RES-SMD-0805")
      (description "Resistor")
      (fields
        (field (name "MANUFACTURER") "Generic Components")
        (field (name "PUBLISHER") "Altium Hobart Technology Centre")
      )
      (libsource (lib "RAL") (part "Res-SMD"))
    )
    (comp (ref "R78")
      (value "2M")
      (footprint "RES-SMD-1206")
      (description "Resistor")
      (fields
        (field (name "MANUFACTURER") "Generic Components")
        (field (name "PUBLISHER") "Altium Hobart Technology Centre")
      )
      (libsource (lib "RAL") (part "Res-SMD"))
    )
    (comp (ref "R79")
      (value "10K/2010")
      (footprint "RES-SMD-1206")
      (description "Resistor")
      (fields
        (field (name "MANUFACTURER") "Generic Components")
        (field (name "PUBLISHER") "Altium Hobart Technology Centre")
      )
      (libsource (lib "RAL") (part "Res-SMD"))
    )
    (comp (ref "R80")
      (value "10R/0805")
      (footprint "RES-SMD-0805")
      (description "Resistor")
      (fields
        (field (name "MANUFACTURER") "Generic Components")
        (field (name "PUBLISHER") "Altium Hobart Technology Centre")
      )
      (libsource (lib "RAL") (part "Res-SMD"))
    )
    (comp (ref "R81")
      (value "2M")
      (footprint "RES-SMD-1206")
      (description "Resistor")
      (fields
        (field (name "MANUFACTURER") "Generic Components")
        (field (name "PUBLISHER") "Altium Hobart Technology Centre")
      )
      (libsource (lib "RAL") (part "Res-SMD"))
    )
    (comp (ref "R82")
      (value "0R")
      (footprint "RES-SMD-0805")
      (description "Resistor")
      (fields
        (field (name "MANUFACTURER") "Generic Components")
        (field (name "PUBLISHER") "Altium Hobart Technology Centre")
      )
      (libsource (lib "RAL") (part "Res-SMD"))
    )
    (comp (ref "R83")
      (value "30K")
      (footprint "RES-SMD-0805")
      (description "Resistor")
      (fields
        (field (name "MANUFACTURER") "Generic Components")
        (field (name "PUBLISHER") "Altium Hobart Technology Centre")
      )
      (libsource (lib "RAL") (part "Res-SMD"))
    )
    (comp (ref "R84")
      (value "10R")
      (footprint "RES-SMD-1206")
      (description "Resistor")
      (fields
        (field (name "MANUFACTURER") "Generic Components")
        (field (name "PUBLISHER") "Altium Hobart Technology Centre")
      )
      (libsource (lib "RAL") (part "Res-SMD"))
    )
    (comp (ref "R85")
      (value "10K/0805")
      (footprint "RES-SMD-0805")
      (description "Resistor")
      (fields
        (field (name "MANUFACTURER") "Generic Components")
        (field (name "PUBLISHER") "Altium Hobart Technology Centre")
      )
      (libsource (lib "RAL") (part "Res-SMD"))
    )
    (comp (ref "R86")
      (value "2M")
      (footprint "RES-SMD-1206")
      (description "Resistor")
      (fields
        (field (name "MANUFACTURER") "Generic Components")
        (field (name "PUBLISHER") "Altium Hobart Technology Centre")
      )
      (libsource (lib "RAL") (part "Res-SMD"))
    )
    (comp (ref "R87")
      (value "5.1K/0805")
      (footprint "RES-SMD-0805 EX")
      (description "Resistor")
      (fields
        (field (name "MANUFACTURER") "Generic Components")
        (field (name "PUBLISHER") "Altium Hobart Technology Centre")
      )
      (libsource (lib "RAL") (part "Res-SMD"))
    )
    (comp (ref "R88")
      (value "1K")
      (footprint "RES-SMD-1210")
      (description "Resistor")
      (fields
        (field (name "MANUFACTURER") "Generic Components")
        (field (name "PUBLISHER") "Altium Hobart Technology Centre")
      )
      (libsource (lib "RAL") (part "Res-SMD"))
    )
    (comp (ref "R89")
      (value "100R")
      (footprint "RES-SMD-0805")
      (description "Resistor")
      (fields
        (field (name "MANUFACTURER") "Generic Components")
        (field (name "PUBLISHER") "Altium Hobart Technology Centre")
      )
      (libsource (lib "RAL") (part "Res-SMD"))
    )
    (comp (ref "R90")
      (value "150R/1206")
      (footprint "RES-SMD-1206")
      (description "Resistor")
      (fields
        (field (name "MANUFACTURER") "Generic Components")
        (field (name "PUBLISHER") "Altium Hobart Technology Centre")
      )
      (libsource (lib "RAL") (part "Res-SMD"))
    )
    (comp (ref "R91")
      (value "150R/1206")
      (footprint "RES-SMD-1206")
      (description "Resistor")
      (fields
        (field (name "MANUFACTURER") "Generic Components")
        (field (name "PUBLISHER") "Altium Hobart Technology Centre")
      )
      (libsource (lib "RAL") (part "Res-SMD"))
    )
    (comp (ref "R92")
      (value "10R/0805")
      (footprint "RES-SMD-0805")
      (description "Resistor")
      (fields
        (field (name "MANUFACTURER") "Generic Components")
        (field (name "PUBLISHER") "Altium Hobart Technology Centre")
      )
      (libsource (lib "RAL") (part "Res-SMD"))
    )
    (comp (ref "R93")
      (value "0.33R/2010")
      (footprint "RES-SMD-1210")
      (description "Resistor")
      (fields
        (field (name "MANUFACTURER") "Generic Components")
        (field (name "PUBLISHER") "Altium Hobart Technology Centre")
      )
      (libsource (lib "RAL") (part "Res-SMD"))
    )
    (comp (ref "R94")
      (value "0.33R/2010")
      (footprint "RES-SMD-1210")
      (description "Resistor")
      (fields
        (field (name "MANUFACTURER") "Generic Components")
        (field (name "PUBLISHER") "Altium Hobart Technology Centre")
      )
      (libsource (lib "RAL") (part "Res-SMD"))
    )
    (comp (ref "R95")
      (value "0R")
      (footprint "RES-SMD-1206")
      (description "Resistor")
      (fields
        (field (name "MANUFACTURER") "Generic Components")
        (field (name "PUBLISHER") "Altium Hobart Technology Centre")
      )
      (libsource (lib "RAL") (part "Res-SMD"))
    )
    (comp (ref "R96")
      (value "2K/1206")
      (footprint "RES-SMD-1206")
      (description "Resistor")
      (fields
        (field (name "MANUFACTURER") "Generic Components")
        (field (name "PUBLISHER") "Altium Hobart Technology Centre")
      )
      (libsource (lib "RAL") (part "Res-SMD"))
    )
    (comp (ref "R97")
      (value "300K")
      (footprint "RES-SMD-0805")
      (description "Resistor")
      (fields
        (field (name "MANUFACTURER") "Generic Components")
        (field (name "PUBLISHER") "Altium Hobart Technology Centre")
      )
      (libsource (lib "RAL") (part "Res-SMD"))
    )
    (comp (ref "R98")
      (value "20K")
      (footprint "RES-SMD-0805")
      (description "Resistor")
      (fields
        (field (name "MANUFACTURER") "Generic Components")
        (field (name "PUBLISHER") "Altium Hobart Technology Centre")
      )
      (libsource (lib "RAL") (part "Res-SMD"))
    )
    (comp (ref "R99")
      (value "5.1K")
      (footprint "RES-SMD-0805")
      (description "Resistor")
      (fields
        (field (name "MANUFACTURER") "Generic Components")
        (field (name "PUBLISHER") "Altium Hobart Technology Centre")
      )
      (libsource (lib "RAL") (part "Res-SMD"))
    )
    (comp (ref "R100")
      (value "100K")
      (footprint "RES-SMD-0805")
      (description "Resistor")
      (fields
        (field (name "MANUFACTURER") "Generic Components")
        (field (name "PUBLISHER") "Altium Hobart Technology Centre")
      )
      (libsource (lib "RAL") (part "Res-SMD"))
    )
    (comp (ref "R101")
      (value "15K")
      (footprint "RES-SMD-0805")
      (description "Resistor")
      (fields
        (field (name "MANUFACTURER") "Generic Components")
        (field (name "PUBLISHER") "Altium Hobart Technology Centre")
      )
      (libsource (lib "RAL") (part "Res-SMD"))
    )
    (comp (ref "R102")
      (value "5.1K/1206")
      (footprint "RES-SMD-1206")
      (description "Resistor")
      (fields
        (field (name "MANUFACTURER") "Generic Components")
        (field (name "PUBLISHER") "Altium Hobart Technology Centre")
      )
      (libsource (lib "RAL") (part "Res-SMD"))
    )
    (comp (ref "R103")
      (value "30R/1206")
      (footprint "RES-SMD-1206")
      (description "Resistor")
      (fields
        (field (name "MANUFACTURER") "Generic Components")
        (field (name "PUBLISHER") "Altium Hobart Technology Centre")
      )
      (libsource (lib "RAL") (part "Res-SMD"))
    )
    (comp (ref "R104")
      (value "510R")
      (footprint "RES-SMD-0805")
      (description "Resistor")
      (fields
        (field (name "MANUFACTURER") "Generic Components")
        (field (name "PUBLISHER") "Altium Hobart Technology Centre")
      )
      (libsource (lib "RAL") (part "Res-SMD"))
    )
    (comp (ref "R105")
      (value "5.1K")
      (footprint "RES-SMD-0805")
      (description "Resistor")
      (fields
        (field (name "MANUFACTURER") "Generic Components")
        (field (name "PUBLISHER") "Altium Hobart Technology Centre")
      )
      (libsource (lib "RAL") (part "Res-SMD"))
    )
    (comp (ref "R106")
      (value "20k")
      (footprint "RES-SMD-0805")
      (description "Resistor")
      (fields
        (field (name "MANUFACTURER") "Generic Components")
        (field (name "PUBLISHER") "Altium Hobart Technology Centre")
      )
      (libsource (lib "RAL") (part "Res-SMD"))
    )
    (comp (ref "R107")
      (value "100R")
      (footprint "RES-SMD-0805")
      (description "Resistor")
      (fields
        (field (name "MANUFACTURER") "Generic Components")
        (field (name "PUBLISHER") "Altium Hobart Technology Centre")
      )
      (libsource (lib "RAL") (part "Res-SMD"))
    )
    (comp (ref "R108")
      (value "10K/0805")
      (footprint "RES-SMD-0805")
      (description "Resistor")
      (fields
        (field (name "MANUFACTURER") "Generic Components")
        (field (name "PUBLISHER") "Altium Hobart Technology Centre")
      )
      (libsource (lib "RAL") (part "Res-SMD"))
    )
    (comp (ref "R109")
      (value "430R")
      (footprint "RES-SMD-0805")
      (description "Resistor")
      (fields
        (field (name "MANUFACTURER") "Generic Components")
        (field (name "PUBLISHER") "Altium Hobart Technology Centre")
      )
      (libsource (lib "RAL") (part "Res-SMD"))
    )
    (comp (ref "R110")
      (value "510R")
      (footprint "RES-SMD-0805")
      (description "Resistor")
      (fields
        (field (name "MANUFACTURER") "Generic Components")
        (field (name "PUBLISHER") "Altium Hobart Technology Centre")
      )
      (libsource (lib "RAL") (part "Res-SMD"))
    )
    (comp (ref "R111")
      (value "5.1K")
      (footprint "RES-SMD-0805")
      (description "Resistor")
      (fields
        (field (name "MANUFACTURER") "Generic Components")
        (field (name "PUBLISHER") "Altium Hobart Technology Centre")
      )
      (libsource (lib "RAL") (part "Res-SMD"))
    )
    (comp (ref "R112")
      (value "4.3K")
      (footprint "RES-SMD-0805")
      (description "Resistor")
      (fields
        (field (name "MANUFACTURER") "Generic Components")
        (field (name "PUBLISHER") "Altium Hobart Technology Centre")
      )
      (libsource (lib "RAL") (part "Res-SMD"))
    )
    (comp (ref "R113")
      (value "10R/0805")
      (footprint "RES-SMD-0805")
      (description "Resistor")
      (fields
        (field (name "MANUFACTURER") "Generic Components")
        (field (name "PUBLISHER") "Altium Hobart Technology Centre")
      )
      (libsource (lib "RAL") (part "Res-SMD"))
    )
    (comp (ref "R114")
      (value "100R")
      (footprint "RES-SMD-0805")
      (description "Resistor")
      (fields
        (field (name "MANUFACTURER") "Generic Components")
        (field (name "PUBLISHER") "Altium Hobart Technology Centre")
      )
      (libsource (lib "RAL") (part "Res-SMD"))
    )
    (comp (ref "R115")
      (value "1K")
      (footprint "RES-SMD-0805")
      (description "Resistor")
      (fields
        (field (name "MANUFACTURER") "Generic Components")
        (field (name "PUBLISHER") "Altium Hobart Technology Centre")
      )
      (libsource (lib "RAL") (part "Res-SMD"))
    )
    (comp (ref "R116")
      (value "100K")
      (footprint "RES-SMD-0805")
      (description "Resistor")
      (fields
        (field (name "MANUFACTURER") "Generic Components")
        (field (name "PUBLISHER") "Altium Hobart Technology Centre")
      )
      (libsource (lib "RAL") (part "Res-SMD"))
    )
    (comp (ref "R117")
      (value "0.33R/2010")
      (footprint "RES-SMD-1210 EX")
      (description "Resistor")
      (fields
        (field (name "MANUFACTURER") "Generic Components")
        (field (name "PUBLISHER") "Altium Hobart Technology Centre")
      )
      (libsource (lib "RAL") (part "Res-SMD"))
    )
    (comp (ref "R118")
      (value "0.33R/2010")
      (footprint "RES-SMD-1210 EX")
      (description "Resistor")
      (fields
        (field (name "MANUFACTURER") "Generic Components")
        (field (name "PUBLISHER") "Altium Hobart Technology Centre")
      )
      (libsource (lib "RAL") (part "Res-SMD"))
    )
    (comp (ref "R119")
      (value "0.33R/2010")
      (footprint "RES-SMD-1210 EX")
      (description "Resistor")
      (fields
        (field (name "MANUFACTURER") "Generic Components")
        (field (name "PUBLISHER") "Altium Hobart Technology Centre")
      )
      (libsource (lib "RAL") (part "Res-SMD"))
    )
    (comp (ref "R120")
      (value "0.33R/2010")
      (footprint "RES-SMD-1210 EX")
      (description "Resistor")
      (fields
        (field (name "MANUFACTURER") "Generic Components")
        (field (name "PUBLISHER") "Altium Hobart Technology Centre")
      )
      (libsource (lib "RAL") (part "Res-SMD"))
    )
    (comp (ref "R121")
      (value "5.1K")
      (footprint "RES-SMD-0805")
      (description "Resistor")
      (fields
        (field (name "MANUFACTURER") "Generic Components")
        (field (name "PUBLISHER") "Altium Hobart Technology Centre")
      )
      (libsource (lib "RAL") (part "Res-SMD"))
    )
    (comp (ref "R122")
      (value "22R")
      (footprint "RES-SMD-0805")
      (description "Resistor")
      (fields
        (field (name "MANUFACTURER") "Generic Components")
        (field (name "PUBLISHER") "Altium Hobart Technology Centre")
      )
      (libsource (lib "RAL") (part "Res-SMD"))
    )
    (comp (ref "R123")
      (value "1K")
      (footprint "RES-SMD-0805")
      (description "Resistor")
      (fields
        (field (name "MANUFACTURER") "Generic Components")
        (field (name "PUBLISHER") "Altium Hobart Technology Centre")
      )
      (libsource (lib "RAL") (part "Res-SMD"))
    )
    (comp (ref "R124")
      (value "10K/0805")
      (footprint "RES-SMD-0805")
      (description "Resistor")
      (fields
        (field (name "MANUFACTURER") "Generic Components")
        (field (name "PUBLISHER") "Altium Hobart Technology Centre")
      )
      (libsource (lib "RAL") (part "Res-SMD"))
    )
    (comp (ref "R125")
      (value "4.3K")
      (footprint "RES-SMD-0805")
      (description "Resistor")
      (fields
        (field (name "MANUFACTURER") "Generic Components")
        (field (name "PUBLISHER") "Altium Hobart Technology Centre")
      )
      (libsource (lib "RAL") (part "Res-SMD"))
    )
    (comp (ref "R126")
      (value "1.3K")
      (footprint "RES-SMD-0805")
      (description "Resistor")
      (fields
        (field (name "MANUFACTURER") "Generic Components")
        (field (name "PUBLISHER") "Altium Hobart Technology Centre")
      )
      (libsource (lib "RAL") (part "Res-SMD"))
    )
    (comp (ref "R127")
      (value "10K/1206")
      (footprint "RES-SMD-1206")
      (description "Resistor")
      (fields
        (field (name "MANUFACTURER") "Generic Components")
        (field (name "PUBLISHER") "Altium Hobart Technology Centre")
      )
      (libsource (lib "RAL") (part "Res-SMD"))
    )
    (comp (ref "R128")
      (value "30K")
      (footprint "RES-SMD-0805")
      (description "Resistor")
      (fields
        (field (name "MANUFACTURER") "Generic Components")
        (field (name "PUBLISHER") "Altium Hobart Technology Centre")
      )
      (libsource (lib "RAL") (part "Res-SMD"))
    )
    (comp (ref "R129")
      (value "1K")
      (footprint "RES-SMD-0805")
      (description "Resistor")
      (fields
        (field (name "MANUFACTURER") "Generic Components")
        (field (name "PUBLISHER") "Altium Hobart Technology Centre")
      )
      (libsource (lib "RAL") (part "Res-SMD"))
    )
    (comp (ref "R130")
      (value "100K")
      (footprint "RES-SMD-0805")
      (description "Resistor")
      (fields
        (field (name "MANUFACTURER") "Generic Components")
        (field (name "PUBLISHER") "Altium Hobart Technology Centre")
      )
      (libsource (lib "RAL") (part "Res-SMD"))
    )
    (comp (ref "R131")
      (value "100K/1210")
      (footprint "RES-SMD-1210")
      (description "Resistor")
      (fields
        (field (name "MANUFACTURER") "Generic Components")
        (field (name "PUBLISHER") "Altium Hobart Technology Centre")
      )
      (libsource (lib "RAL") (part "Res-SMD"))
    )
    (comp (ref "R132")
      (value "499K/1206")
      (footprint "RES-SMD-1206")
      (description "Resistor")
      (fields
        (field (name "MANUFACTURER") "Generic Components")
        (field (name "PUBLISHER") "Altium Hobart Technology Centre")
      )
      (libsource (lib "RAL") (part "Res-SMD"))
    )
    (comp (ref "R133")
      (value "499K/1206")
      (footprint "RES-SMD-1206")
      (description "Resistor")
      (fields
        (field (name "MANUFACTURER") "Generic Components")
        (field (name "PUBLISHER") "Altium Hobart Technology Centre")
      )
      (libsource (lib "RAL") (part "Res-SMD"))
    )
    (comp (ref "R134")
      (value "499K/1206")
      (footprint "RES-SMD-1206")
      (description "Resistor")
      (fields
        (field (name "MANUFACTURER") "Generic Components")
        (field (name "PUBLISHER") "Altium Hobart Technology Centre")
      )
      (libsource (lib "RAL") (part "Res-SMD"))
    )
    (comp (ref "R135")
      (value "499K/1206")
      (footprint "RES-SMD-1206")
      (description "Resistor")
      (fields
        (field (name "MANUFACTURER") "Generic Components")
        (field (name "PUBLISHER") "Altium Hobart Technology Centre")
      )
      (libsource (lib "RAL") (part "Res-SMD"))
    )
    (comp (ref "R136")
      (value "100K")
      (footprint "RES-SMD-0805")
      (description "Resistor")
      (fields
        (field (name "MANUFACTURER") "Generic Components")
        (field (name "PUBLISHER") "Altium Hobart Technology Centre")
      )
      (libsource (lib "RAL") (part "Res-SMD"))
    )
    (comp (ref "R137")
      (value "100K/1210")
      (footprint "RES-SMD-1210")
      (description "Resistor")
      (fields
        (field (name "MANUFACTURER") "Generic Components")
        (field (name "PUBLISHER") "Altium Hobart Technology Centre")
      )
      (libsource (lib "RAL") (part "Res-SMD"))
    )
    (comp (ref "R138")
      (value "100K/1210")
      (footprint "RES-SMD-1210")
      (description "Resistor")
      (fields
        (field (name "MANUFACTURER") "Generic Components")
        (field (name "PUBLISHER") "Altium Hobart Technology Centre")
      )
      (libsource (lib "RAL") (part "Res-SMD"))
    )
    (comp (ref "R139")
      (value "499K/1206")
      (footprint "RES-SMD-1206")
      (description "Resistor")
      (fields
        (field (name "MANUFACTURER") "Generic Components")
        (field (name "PUBLISHER") "Altium Hobart Technology Centre")
      )
      (libsource (lib "RAL") (part "Res-SMD"))
    )
    (comp (ref "R140")
      (value "499K/1206")
      (footprint "RES-SMD-1206")
      (description "Resistor")
      (fields
        (field (name "MANUFACTURER") "Generic Components")
        (field (name "PUBLISHER") "Altium Hobart Technology Centre")
      )
      (libsource (lib "RAL") (part "Res-SMD"))
    )
    (comp (ref "R141")
      (value "499K/1206")
      (footprint "RES-SMD-1206")
      (description "Resistor")
      (fields
        (field (name "MANUFACTURER") "Generic Components")
        (field (name "PUBLISHER") "Altium Hobart Technology Centre")
      )
      (libsource (lib "RAL") (part "Res-SMD"))
    )
    (comp (ref "R142")
      (value "499K/1206")
      (footprint "RES-SMD-1206")
      (description "Resistor")
      (fields
        (field (name "MANUFACTURER") "Generic Components")
        (field (name "PUBLISHER") "Altium Hobart Technology Centre")
      )
      (libsource (lib "RAL") (part "Res-SMD"))
    )
    (comp (ref "R144")
      (value "100K/1210")
      (footprint "RES-SMD-1210")
      (description "Resistor")
      (fields
        (field (name "MANUFACTURER") "Generic Components")
        (field (name "PUBLISHER") "Altium Hobart Technology Centre")
      )
      (libsource (lib "RAL") (part "Res-SMD"))
    )
    (comp (ref "R145")
      (value "100K")
      (footprint "RES-SMD-0805")
      (description "Resistor")
      (fields
        (field (name "MANUFACTURER") "Generic Components")
        (field (name "PUBLISHER") "Altium Hobart Technology Centre")
      )
      (libsource (lib "RAL") (part "Res-SMD"))
    )
    (comp (ref "R146")
      (value "0R")
      (footprint "RES-SMD-0805")
      (description "Resistor")
      (fields
        (field (name "MANUFACTURER") "Generic Components")
        (field (name "PUBLISHER") "Altium Hobart Technology Centre")
      )
      (libsource (lib "RAL") (part "Res-SMD"))
    )
    (comp (ref "RV1")
      (value "S20K420")
      (footprint "VAR_B72220S0301K101")
      (description "Varistor 420VAC 8000A(8/20us) B72220S0421K101")
      (fields (field (name "MP") "B72220S0301K101") (field (name "MF") "TDK"))
      (libsource (lib "Lib_RD_Cg") (part "Varistor B772"))
    )
    (comp (ref "RV2")
      (value "S20K420")
      (footprint "VAR_B72220S0301K101")
      (description "Varistor 420VAC 8000A(8/20us) B72220S0421K101")
      (fields (field (name "MP") "B72220S0301K101") (field (name "MF") "TDK"))
      (libsource (lib "Lib_RD_Cg") (part "Varistor B772"))
    )
    (comp (ref "RV3")
      (value "S20K420")
      (footprint "VAR_B72220S0301K101")
      (description "Varistor 420VAC 8000A(8/20us) B72220S0421K101")
      (fields (field (name "MP") "B72220S0301K101") (field (name "MF") "TDK"))
      (libsource (lib "Lib_RD_Cg") (part "Varistor B772"))
    )
    (comp (ref "RV4")
      (value "S20K420")
      (footprint "VAR_B72220S0301K101")
      (description "Varistor 420VAC 8000A(8/20us) B72220S0421K101")
      (fields (field (name "MP") "B72220S0301K101") (field (name "MF") "TDK"))
      (libsource (lib "Lib_RD_Cg") (part "Varistor B772"))
    )
    (comp (ref "T1")
      (value "Tranf6")
      (footprint "tranf6")
      (description "Off-Line Transformer WE-UNIT , L=0.9mH")
      (fields
        (field (name "PARTNO") "749118205")
        (field (name "MANUFACTURER") "Würth Elektronik eiSos GmbH")
        (field (name "CREATED BY") "Otto Christin")
      )
      (libsource (lib "Lib_RD_Cg") (part "Tranf6"))
    )
    (comp (ref "U1")
      (value "PVSS STK-PL")
      (footprint "SENSOR-STK-PL")
      (description "Current Sensor sinomags STK-PL 50")
      (fields (field (name "DESIGNED BY") "VanDungEvn"))
      (libsource (lib "") (part "Sensor STK-PL_1"))
    )
    (comp (ref "U2")
      (value "ULN2003A")
      (footprint "SO16")
      (description "Power Switch/Driver 1:1 Darlington 500mA 16-SOP")
      (fields (field (name "MF") "UMW"))
      (libsource (lib "Lib_RD_Cg") (part "ULN2003A"))
    )
    (comp (ref "U3")
      (value "78M05")
      (footprint "TO252")
      (description "UTC 78D05AAL")
      (libsource (lib "Altium_Lib_by_KhueNguyenCreator") (part "78M05 SMD TO252"))
    )
    (comp (ref "U4")
      (value "LF347")
      (footprint "SO14")
      (description "Low Power Quad Operational Amplifier")
      (fields
        (field (name "MANUFACTURER PART NUMBER") "LF347BD")
        (field (name "MANUFACTURER") "Texas Instruments")
      )
      (libsource (lib "TechMT.VN_Lib_Project v2") (part "LF347"))
    )
    (comp (ref "U5")
      (value "MC7912BD2T")
      (footprint "TO263_123")
      (description "IC -12V")
      (fields (field (name "PUBLISHER") "Altium Limited"))
      (libsource (lib "Lib_RD_Cg") (part "7133_1"))
    )
    (comp (ref "U6")
      (value "ICE3AR0680jz")
      (footprint "PG-DIP-7_L9.5-W6.4-P2.54-LS7.6-BL-PE6")
      (description "HIGH PERFORMANCE CURRENT MODE PWM CONTROLLER")
      (fields (field (name "MP") "UC2845BD1"))
      (libsource (lib "Lib_RD_Cg") (part "ICE3AR0680jz"))
    )
    (comp (ref "U7")
      (value "UC2845A")
      (footprint "SOIC127P600X175-8N")
      (fields (field (name "MF") "ON Semiconductor") (field (name "MP") "UC3843BVD1G"))
      (libsource (lib "Lib_RD_Cg") (part "UC3843BVD1G"))
    )
    (comp (ref "U8")
      (value "617A-3")
      (footprint "OPTO TRANSISTOR_SMD-4")
      (description "OPTOISOLATOR 3.75KV TRANS 4-SOP")
      (fields (field (name "MPN") "VOM617A-2T"))
      (libsource (lib "BYTECH_HW_LIB_2019 (1)") (part "VOM617A-2T"))
    )
    (comp (ref "U9")
      (value "TL431BIDR")
      (footprint "SOIC127P600X175-8N")
      (fields (field (name "MF") "ON Semiconductor") (field (name "MP") "TL431BIDR2G"))
      (libsource (lib "Lib_RD_Cg") (part "TL431BIDR2G"))
    )
    (comp (ref "U10")
      (value "Sensor STK-PL")
      (footprint "SENSOR-STK-PL")
      (description "Current Sensor sinomags STK-PL 50")
      (fields (field (name "DESIGNED BY") "VanDungEvn"))
      (libsource (lib "Lib_RD_Cg") (part "Sensor STK-PL"))
    )
    (comp (ref "VR1")
      (value "EPCOS")
      (footprint "Cap EPCOS 21")
      (description "Chống sét lan truyền B88069X4880S102(ví dụ)")
      (fields (field (name "MP") "B72220S0301K101") (field (name "MF") "TDK"))
      (libsource (lib "Lib_RD_Cg") (part "Varistor B772"))
    )
  )
  (nets
    (net (code "1") (name "+5V") (class "Default")
      (node (ref "C2") (pin "1") (pinfunction "1_1") (pintype "passive"))
      (node (ref "C40") (pin "1") (pinfunction "1_1") (pintype "passive"))
      (node (ref "C49") (pin "1") (pinfunction "1_1") (pintype "passive"))
      (node (ref "C65") (pin "2") (pinfunction "2_2") (pintype "passive"))
      (node (ref "C82") (pin "1") (pinfunction "1_1") (pintype "passive"))
      (node (ref "H8") (pin "15") (pinfunction "15_15") (pintype "passive"))
      (node (ref "H8") (pin "16") (pinfunction "16_16") (pintype "passive"))
      (node (ref "R102") (pin "2") (pinfunction "2_2") (pintype "passive"))
      (node (ref "R66") (pin "2") (pinfunction "2_2") (pintype "passive"))
      (node (ref "R76") (pin "2") (pinfunction "2_2") (pintype "passive"))
      (node (ref "R77") (pin "2") (pinfunction "2_2") (pintype "passive"))
      (node (ref "R96") (pin "2") (pinfunction "2_2") (pintype "passive"))
      (node (ref "U1") (pin "4") (pinfunction "Vcc_4") (pintype "passive"))
      (node (ref "U10") (pin "4") (pinfunction "Vcc_4") (pintype "passive"))
      (node (ref "U3") (pin "3") (pinfunction "OUT_3") (pintype "power_in"))
    )
    (net (code "2") (name "+10V") (class "Default")
      (node (ref "C42") (pin "1") (pinfunction "1_1") (pintype "passive"))
      (node (ref "C43") (pin "1") (pinfunction "1_1") (pintype "passive"))
      (node (ref "C44") (pin "1") (pinfunction "1_1") (pintype "passive"))
      (node (ref "C45") (pin "1") (pinfunction "1_1") (pintype "passive"))
      (node (ref "C46") (pin "1") (pinfunction "1_1") (pintype "passive"))
      (node (ref "C47") (pin "1") (pinfunction "1_1") (pintype "passive"))
      (node (ref "C48") (pin "1") (pinfunction "1_1") (pintype "passive"))
      (node (ref "D1") (pin "1") (pinfunction "A_1") (pintype "passive"))
      (node (ref "D14") (pin "3") (pinfunction "K_3") (pintype "passive"))
      (node (ref "D4") (pin "3") (pinfunction "K_3") (pintype "passive"))
      (node (ref "R114") (pin "1") (pinfunction "1_1") (pintype "passive"))
      (node (ref "R123") (pin "1") (pinfunction "1_1") (pintype "passive"))
      (node (ref "R79") (pin "1") (pinfunction "1_1") (pintype "passive"))
      (node (ref "R8") (pin "1") (pinfunction "1_1") (pintype "passive"))
      (node (ref "R98") (pin "1") (pinfunction "1_1") (pintype "passive"))
      (node (ref "U3") (pin "1") (pinfunction "IN_1") (pintype "power_in"))
    )
    (net (code "3") (name "+12V") (class "Default")
      (node (ref "C18") (pin "1") (pinfunction "1_1") (pintype "passive"))
      (node (ref "C41") (pin "1") (pinfunction "1_1") (pintype "passive"))
      (node (ref "C67") (pin "2") (pinfunction "2_2") (pintype "passive"))
      (node (ref "C68") (pin "2") (pinfunction "2_2") (pintype "passive"))
      (node (ref "C69") (pin "1") (pinfunction "1_1") (pintype "passive"))
      (node (ref "C70") (pin "1") (pinfunction "1_1") (pintype "passive"))
      (node (ref "D21") (pin "3") (pinfunction "K_3") (pintype "passive"))
      (node (ref "H1") (pin "2") (pinfunction "2_2") (pintype "passive"))
      (node (ref "H3") (pin "4") (pinfunction "4_4") (pintype "passive"))
      (node (ref "H6") (pin "4") (pinfunction "4_4") (pintype "passive"))
      (node (ref "H8") (pin "17") (pinfunction "17_17") (pintype "passive"))
      (node (ref "L1") (pin "1") (pinfunction "1_1") (pintype "passive"))
      (node (ref "R100") (pin "2") (pinfunction "2_2") (pintype "passive"))
      (node (ref "R91") (pin "1") (pinfunction "1_1") (pintype "passive"))
      (node (ref "U4") (pin "4") (pinfunction "VCC_4") (pintype "power_in"))
    )
    (net (code "4") (name "-12V") (class "Default")
      (node (ref "C56") (pin "2") (pinfunction "2_2") (pintype "passive"))
      (node (ref "C57") (pin "1") (pinfunction "1_1") (pintype "passive"))
      (node (ref "H8") (pin "13") (pinfunction "13_13") (pintype "passive"))
      (node (ref "U4") (pin "11") (pinfunction "VEE_11") (pintype "power_in"))
      (node (ref "U5") (pin "3") (pinfunction "OUT_3") (pintype "power_in"))
    )
    (net (code "5") (name "/CTR_Relay") (class "Default")
      (node (ref "H8") (pin "18") (pinfunction "18_18") (pintype "passive"))
      (node (ref "R6") (pin "1") (pinfunction "1_1") (pintype "passive"))
    )
    (net (code "6") (name "/Ctr_Fan1") (class "Default")
      (node (ref "H8") (pin "22") (pinfunction "22_22") (pintype "passive"))
      (node (ref "R80") (pin "1") (pinfunction "1_1") (pintype "passive"))
      (node (ref "R85") (pin "1") (pinfunction "1_1") (pintype "passive"))
      (node (ref "R92") (pin "1") (pinfunction "1_1") (pintype "passive"))
    )
    (net (code "7") (name "/Ctr_Fan2") (class "Default")
      (node (ref "H8") (pin "24") (pinfunction "24_24") (pintype "passive"))
      (node (ref "R113") (pin "1") (pinfunction "1_1") (pintype "passive"))
      (node (ref "R124") (pin "1") (pinfunction "1_1") (pintype "passive"))
      (node (ref "R92") (pin "2") (pinfunction "2_2") (pintype "passive"))
    )
    (net (code "8") (name "/EVN_L") (class "Default")
      (node (ref "H8") (pin "7") (pinfunction "7_7") (pintype "passive"))
      (node (ref "R9") (pin "2") (pinfunction "2_2") (pintype "passive"))
    )
    (net (code "9") (name "/EVN_N") (class "Default")
      (node (ref "H8") (pin "8") (pinfunction "8_8") (pintype "passive"))
      (node (ref "R31") (pin "2") (pinfunction "2_2") (pintype "passive"))
    )
    (net (code "10") (name "/Fan_Ss") (class "Default")
      (node (ref "D15") (pin "3") (pinfunction "K_3") (pintype "passive"))
      (node (ref "H8") (pin "12") (pinfunction "12_12") (pintype "passive"))
      (node (ref "R87") (pin "2") (pinfunction "2_2") (pintype "passive"))
    )
    (net (code "11") (name "/L_Out") (class "Default")
      (node (ref "H8") (pin "5") (pinfunction "5_5") (pintype "passive"))
      (node (ref "R23") (pin "2") (pinfunction "2_2") (pintype "passive"))
    )
    (net (code "12") (name "/N_Out") (class "Default")
      (node (ref "H8") (pin "6") (pinfunction "6_6") (pintype "passive"))
      (node (ref "R30") (pin "2") (pinfunction "2_2") (pintype "passive"))
    )
    (net (code "13") (name "/PE PV") (class "Default")
      (node (ref "C30") (pin "1") (pinfunction "1_1") (pintype "passive"))
      (node (ref "C31") (pin "1") (pinfunction "1_1") (pintype "passive"))
      (node (ref "C35") (pin "1") (pinfunction "1_1") (pintype "passive"))
      (node (ref "C36") (pin "1") (pinfunction "1_1") (pintype "passive"))
      (node (ref "C86") (pin "2") (pinfunction "2_2") (pintype "passive"))
      (node (ref "C87") (pin "1") (pinfunction "1_1") (pintype "passive"))
      (node (ref "C90") (pin "1") (pinfunction "1_1") (pintype "passive"))
      (node (ref "C91") (pin "2") (pinfunction "2_2") (pintype "passive"))
      (node (ref "M5") (pin "1") (pinfunction "1_1") (pintype "passive"))
    )
    (net (code "14") (name "/PE_Bus+") (class "Default")
      (node (ref "H8") (pin "4") (pinfunction "4_4") (pintype "passive"))
      (node (ref "R52") (pin "2") (pinfunction "2_2") (pintype "passive"))
    )
    (net (code "15") (name "/PV+") (class "Default")
      (node (ref "H8") (pin "10") (pinfunction "10_10") (pintype "passive"))
      (node (ref "R132") (pin "1") (pinfunction "1_1") (pintype "passive"))
    )
    (net (code "16") (name "/PV-") (class "Default")
      (node (ref "H8") (pin "9") (pinfunction "9_9") (pintype "passive"))
      (node (ref "R139") (pin "1") (pinfunction "1_1") (pintype "passive"))
    )
    (net (code "17") (name "/RL-K1") (class "Default")
      (node (ref "K4") (pin "2") (pinfunction "2_2") (pintype "passive"))
      (node (ref "U2") (pin "13") (pinfunction "OUT4_13") (pintype "passive"))
      (node (ref "U2") (pin "14") (pinfunction "OUT3_14") (pintype "passive"))
    )
    (net (code "18") (name "/RL-K2") (class "Default")
      (node (ref "K2") (pin "2") (pinfunction "2_2") (pintype "passive"))
      (node (ref "U2") (pin "15") (pinfunction "OUT2_15") (pintype "passive"))
      (node (ref "U2") (pin "16") (pinfunction "OUT1_16") (pintype "passive"))
    )
    (net (code "19") (name "/RL-K3") (class "Default")
      (node (ref "K5") (pin "3") (pinfunction "3_3") (pintype "passive"))
      (node (ref "U2") (pin "12") (pinfunction "OUT5_12") (pintype "passive"))
    )
    (net (code "20") (name "/RL-K4") (class "Default")
      (node (ref "K1") (pin "3") (pinfunction "3_3") (pintype "passive"))
      (node (ref "U2") (pin "11") (pinfunction "OUT6_11") (pintype "passive"))
    )
    (net (code "21") (name "/Relay_1") (class "Default")
      (node (ref "H8") (pin "28") (pinfunction "28_28") (pintype "passive"))
      (node (ref "R15") (pin "2") (pinfunction "2_2") (pintype "passive"))
      (node (ref "R18") (pin "1") (pinfunction "1_1") (pintype "passive"))
      (node (ref "R19") (pin "2") (pinfunction "2_2") (pintype "passive"))
    )
    (net (code "22") (name "/Relay_2") (class "Default")
      (node (ref "H8") (pin "27") (pinfunction "27_27") (pintype "passive"))
      (node (ref "R24") (pin "2") (pinfunction "2_2") (pintype "passive"))
      (node (ref "R35") (pin "1") (pinfunction "1_1") (pintype "passive"))
      (node (ref "R36") (pin "2") (pinfunction "2_2") (pintype "passive"))
    )
    (net (code "23") (name "/Relay_3") (class "Default")
      (node (ref "H8") (pin "26") (pinfunction "26_26") (pintype "passive"))
      (node (ref "R39") (pin "2") (pinfunction "2_2") (pintype "passive"))
      (node (ref "R44") (pin "1") (pinfunction "1_1") (pintype "passive"))
    )
    (net (code "24") (name "/Relay_4") (class "Default")
      (node (ref "H8") (pin "25") (pinfunction "25_25") (pintype "passive"))
      (node (ref "R47") (pin "2") (pinfunction "2_2") (pintype "passive"))
      (node (ref "R48") (pin "1") (pinfunction "1_1") (pintype "passive"))
    )
    (net (code "25") (name "/Relay_5") (class "Default")
      (node (ref "H8") (pin "23") (pinfunction "23_23") (pintype "passive"))
      (node (ref "R51") (pin "2") (pinfunction "2_2") (pintype "passive"))
      (node (ref "R53") (pin "1") (pinfunction "1_1") (pintype "passive"))
    )
    (net (code "26") (name "/Ss_IPV") (class "Default")
      (node (ref "C76") (pin "1") (pinfunction "1_1") (pintype "passive"))
      (node (ref "H8") (pin "11") (pinfunction "11_11") (pintype "passive"))
      (node (ref "R107") (pin "1") (pinfunction "1_1") (pintype "passive"))
    )
    (net (code "27") (name "/Ss_Vout_EVN") (class "Default")
      (node (ref "H8") (pin "1") (pinfunction "1_1") (pintype "passive"))
      (node (ref "R3") (pin "1") (pinfunction "1_1") (pintype "passive"))
    )
    (net (code "28") (name "/Ss_Vref_ENV") (class "Default")
      (node (ref "H8") (pin "2") (pinfunction "2_2") (pintype "passive"))
      (node (ref "R4") (pin "1") (pinfunction "1_1") (pintype "passive"))
    )
    (net (code "29") (name "BAT +48") (class "Default")
      (node (ref "C21") (pin "1") (pinfunction "1_1") (pintype "passive"))
      (node (ref "C22") (pin "2") (pinfunction "2_2") (pintype "passive"))
      (node (ref "C23") (pin "1") (pinfunction "1_1") (pintype "passive"))
      (node (ref "R127") (pin "2") (pinfunction "2_2") (pintype "passive"))
      (node (ref "R130") (pin "1") (pinfunction "1_1") (pintype "passive"))
      (node (ref "R63") (pin "2") (pinfunction "2_2") (pintype "passive"))
      (node (ref "R64") (pin "1") (pinfunction "1_1") (pintype "passive"))
      (node (ref "R82") (pin "1") (pinfunction "1_1") (pintype "passive"))
      (node (ref "T1") (pin "7") (pinfunction "7_7") (pintype "passive"))
    )
    (net (code "30") (name "BUS +") (class "Default")
      (node (ref "D8") (pin "1") (pinfunction "A_1") (pintype "passive"))
      (node (ref "K3") (pin "8") (pinfunction "8_8") (pintype "passive"))
      (node (ref "P8") (pin "1") (pinfunction "1_1") (pintype "passive"))
      (node (ref "R40") (pin "1") (pinfunction "1_1") (pintype "passive"))
    )
    (net (code "31") (name "BUS +10{slash}12V") (class "Default")
      (node (ref "C3") (pin "1") (pinfunction "1_1") (pintype "passive"))
      (node (ref "C4") (pin "2") (pinfunction "2_2") (pintype "passive"))
      (node (ref "C5") (pin "2") (pinfunction "2_2") (pintype "passive"))
      (node (ref "D1") (pin "2") (pinfunction "K_2") (pintype "passive"))
      (node (ref "D2") (pin "2") (pinfunction "A_2") (pintype "passive"))
      (node (ref "K1") (pin "2") (pinfunction "2_2") (pintype "passive"))
      (node (ref "K2") (pin "3") (pinfunction "3_3") (pintype "passive"))
      (node (ref "K4") (pin "3") (pinfunction "3_3") (pintype "passive"))
      (node (ref "K5") (pin "2") (pinfunction "2_2") (pintype "passive"))
      (node (ref "Q1") (pin "2") (pinfunction "C_2") (pintype "passive"))
      (node (ref "R7") (pin "2") (pinfunction "2_2") (pintype "passive"))
    )
    (net (code "32") (name "GND") (class "Default")
      (node (ref "C4") (pin "1") (pinfunction "1_1") (pintype "passive"))
      (node (ref "C41") (pin "2") (pinfunction "2_2") (pintype "passive"))
      (node (ref "C5") (pin "1") (pinfunction "1_1") (pintype "passive"))
      (node (ref "C6") (pin "1") (pinfunction "1_1") (pintype "passive"))
      (node (ref "C9") (pin "1") (pinfunction "1_1") (pintype "passive"))
      (node (ref "H8") (pin "19") (pinfunction "19_19") (pintype "passive"))
      (node (ref "Q2") (pin "3") (pinfunction "E_3") (pintype "passive"))
      (node (ref "R18") (pin "2") (pinfunction "2_2") (pintype "passive"))
      (node (ref "R35") (pin "2") (pinfunction "2_2") (pintype "passive"))
      (node (ref "R44") (pin "2") (pinfunction "2_2") (pintype "passive"))
      (node (ref "R48") (pin "2") (pinfunction "2_2") (pintype "passive"))
      (node (ref "R53") (pin "2") (pinfunction "2_2") (pintype "passive"))
      (node (ref "U2") (pin "8") (pinfunction "GND_8") (pintype "passive"))
    )
    (net (code "33") (name "GND_BAT") (class "Default")
      (node (ref "C20") (pin "1") (pinfunction "1_1") (pintype "passive"))
      (node (ref "C21") (pin "2") (pinfunction "2_2") (pintype "passive"))
      (node (ref "C22") (pin "1") (pinfunction "1_1") (pintype "passive"))
      (node (ref "C35") (pin "2") (pinfunction "2_2") (pintype "passive"))
      (node (ref "C36") (pin "2") (pinfunction "2_2") (pintype "passive"))
      (node (ref "C39") (pin "2") (pinfunction "2_2") (pintype "passive"))
      (node (ref "C51") (pin "1") (pinfunction "1_1") (pintype "passive"))
      (node (ref "C52") (pin "1") (pinfunction "1_1") (pintype "passive"))
      (node (ref "C53") (pin "1") (pinfunction "1_1") (pintype "passive"))
      (node (ref "C66") (pin "2") (pinfunction "2_2") (pintype "passive"))
      (node (ref "C73") (pin "1") (pinfunction "1_1") (pintype "passive"))
      (node (ref "C77") (pin "1") (pinfunction "1_1") (pintype "passive"))
      (node (ref "C79") (pin "1") (pinfunction "1_1") (pintype "passive"))
      (node (ref "C80") (pin "1") (pinfunction "1_1") (pintype "passive"))
      (node (ref "C92") (pin "1") (pinfunction "1_1") (pintype "passive"))
      (node (ref "C93") (pin "2") (pinfunction "2_2") (pintype "passive"))
      (node (ref "D20") (pin "1") (pinfunction "A_1") (pintype "passive"))
      (node (ref "D22") (pin "3") (pinfunction "A_3") (pintype "passive"))
      (node (ref "H2") (pin "3") (pinfunction "3_3") (pintype "passive"))
      (node (ref "H2") (pin "4") (pinfunction "4_4") (pintype "passive"))
      (node (ref "Q6") (pin "3") (pinfunction "E_3") (pintype "passive"))
      (node (ref "Q7") (pin "3") (pinfunction "E_3") (pintype "passive"))
      (node (ref "R108") (pin "2") (pinfunction "2_2") (pintype "passive"))
      (node (ref "R117") (pin "2") (pinfunction "2_2") (pintype "passive"))
      (node (ref "R118") (pin "2") (pinfunction "2_2") (pintype "passive"))
      (node (ref "R119") (pin "2") (pinfunction "2_2") (pintype "passive"))
      (node (ref "R120") (pin "2") (pinfunction "2_2") (pintype "passive"))
      (node (ref "R125") (pin "2") (pinfunction "2_2") (pintype "passive"))
      (node (ref "R145") (pin "2") (pinfunction "2_2") (pintype "passive"))
      (node (ref "R88") (pin "2") (pinfunction "2_2") (pintype "passive"))
      (node (ref "T1") (pin "1") (pinfunction "1_1") (pintype "passive"))
      (node (ref "U7") (pin "5") (pinfunction "GND_5") (pintype "passive"))
    )
    (net (code "34") (name "GND_FB") (class "Default")
      (node (ref "BT1") (pin "17") (pinfunction "17_17") (pintype "passive"))
      (node (ref "C1") (pin "2") (pinfunction "2_2") (pintype "passive"))
      (node (ref "C18") (pin "2") (pinfunction "2_2") (pintype "passive"))
      (node (ref "C2") (pin "2") (pinfunction "2_2") (pintype "passive"))
      (node (ref "C3") (pin "2") (pinfunction "2_2") (pintype "passive"))
      (node (ref "C38") (pin "1") (pinfunction "1_1") (pintype "passive"))
      (node (ref "C40") (pin "2") (pinfunction "2_2") (pintype "passive"))
      (node (ref "C42") (pin "2") (pinfunction "2_2") (pintype "passive"))
      (node (ref "C43") (pin "2") (pinfunction "2_2") (pintype "passive"))
      (node (ref "C44") (pin "2") (pinfunction "2_2") (pintype "passive"))
      (node (ref "C45") (pin "2") (pinfunction "2_2") (pintype "passive"))
      (node (ref "C46") (pin "2") (pinfunction "2_2") (pintype "passive"))
      (node (ref "C47") (pin "2") (pinfunction "2_2") (pintype "passive"))
      (node (ref "C48") (pin "2") (pinfunction "2_2") (pintype "passive"))
      (node (ref "C49") (pin "2") (pinfunction "2_2") (pintype "passive"))
      (node (ref "C54") (pin "1") (pinfunction "1_1") (pintype "passive"))
      (node (ref "C55") (pin "1") (pinfunction "1_1") (pintype "passive"))
      (node (ref "C56") (pin "1") (pinfunction "1_1") (pintype "passive"))
      (node (ref "C57") (pin "2") (pinfunction "2_2") (pintype "passive"))
      (node (ref "C64") (pin "1") (pinfunction "1_1") (pintype "passive"))
      (node (ref "C65") (pin "1") (pinfunction "1_1") (pintype "passive"))
      (node (ref "C67") (pin "1") (pinfunction "1_1") (pintype "passive"))
      (node (ref "C68") (pin "1") (pinfunction "1_1") (pintype "passive"))
      (node (ref "C69") (pin "2") (pinfunction "2_2") (pintype "passive"))
      (node (ref "C70") (pin "2") (pinfunction "2_2") (pintype "passive"))
      (node (ref "C76") (pin "2") (pinfunction "2_2") (pintype "passive"))
      (node (ref "C78") (pin "2") (pinfunction "2_2") (pintype "passive"))
      (node (ref "C82") (pin "2") (pinfunction "2_2") (pintype "passive"))
      (node (ref "H1") (pin "1") (pinfunction "1_1") (pintype "passive"))
      (node (ref "H3") (pin "2") (pinfunction "2_2") (pintype "passive"))
      (node (ref "H6") (pin "2") (pinfunction "2_2") (pintype "passive"))
      (node (ref "H8") (pin "14") (pinfunction "14_14") (pintype "passive"))
      (node (ref "L7") (pin "1") (pinfunction "1_1") (pintype "passive"))
      (node (ref "LED1") (pin "2") (pinfunction "2_2") (pintype "passive"))
      (node (ref "Q3") (pin "3") (pinfunction "E_3") (pintype "passive"))
      (node (ref "Q5") (pin "3") (pinfunction "E_3") (pintype "passive"))
      (node (ref "R121") (pin "2") (pinfunction "2_2") (pintype "passive"))
      (node (ref "R124") (pin "2") (pinfunction "2_2") (pintype "passive"))
      (node (ref "R128") (pin "1") (pinfunction "1_1") (pintype "passive"))
      (node (ref "R129") (pin "1") (pinfunction "1_1") (pintype "passive"))
      (node (ref "R7") (pin "1") (pinfunction "1_1") (pintype "passive"))
      (node (ref "R85") (pin "2") (pinfunction "2_2") (pintype "passive"))
      (node (ref "R87") (pin "1") (pinfunction "1_1") (pintype "passive"))
      (node (ref "U1") (pin "3") (pinfunction "Gnd_3") (pintype "passive"))
      (node (ref "U10") (pin "3") (pinfunction "Gnd_3") (pintype "passive"))
      (node (ref "U3") (pin "2") (pinfunction "GND_2") (pintype "power_in"))
      (node (ref "U4") (pin "10") (pinfunction "3_IN+_10") (pintype "input"))
      (node (ref "U4") (pin "12") (pinfunction "4_IN+_12") (pintype "input"))
      (node (ref "U4") (pin "3") (pinfunction "1_IN+_3") (pintype "input"))
      (node (ref "U5") (pin "1") (pinfunction "GND_1") (pintype "power_in"))
      (node (ref "U9") (pin "2") (pinfunction "A_2") (pintype "passive"))
      (node (ref "U9") (pin "3") (pinfunction "A_3") (pintype "passive"))
      (node (ref "U9") (pin "6") (pinfunction "A_6") (pintype "passive"))
      (node (ref "U9") (pin "7") (pinfunction "A_7") (pintype "passive"))
    )
    (net (code "35") (name "G_2") (class "Default")
      (node (ref "BT1") (pin "5") (pinfunction "5_5") (pintype "passive"))
      (node (ref "C37") (pin "1") (pinfunction "1_1") (pintype "passive"))
      (node (ref "C59") (pin "2") (pinfunction "2_2") (pintype "passive"))
      (node (ref "C61") (pin "1") (pinfunction "1_1") (pintype "passive"))
      (node (ref "C62") (pin "2") (pinfunction "2_2") (pintype "passive"))
      (node (ref "C63") (pin "2") (pinfunction "2_2") (pintype "passive"))
      (node (ref "C81") (pin "1") (pinfunction "1_1") (pintype "passive"))
      (node (ref "L4") (pin "2") (pinfunction "2_2") (pintype "passive"))
      (node (ref "L6") (pin "2") (pinfunction "2_2") (pintype "passive"))
      (node (ref "R93") (pin "2") (pinfunction "2_2") (pintype "passive"))
      (node (ref "R94") (pin "2") (pinfunction "2_2") (pintype "passive"))
      (node (ref "R97") (pin "1") (pinfunction "1_1") (pintype "passive"))
      (node (ref "U6") (pin "8") (pinfunction "GND_8") (pintype "passive"))
      (node (ref "U8") (pin "3") (pinfunction "3_3") (pintype "passive"))
    )
    (net (code "36") (name "NEG") (class "Default")
      (node (ref "C86") (pin "1") (pinfunction "1_1") (pintype "passive"))
      (node (ref "C89") (pin "1") (pinfunction "1_1") (pintype "passive"))
      (node (ref "L6") (pin "1") (pinfunction "1_1") (pintype "passive"))
      (node (ref "L7") (pin "2") (pinfunction "2_2") (pintype "passive"))
      (node (ref "L8") (pin "2") (pinfunction "2_2") (pintype "passive"))
      (node (ref "P12") (pin "1") (pinfunction "1_1") (pintype "passive"))
      (node (ref "R142") (pin "1") (pinfunction "1_1") (pintype "passive"))
      (node (ref "R58") (pin "2") (pinfunction "2_2") (pintype "passive"))
    )
    (net (code "37") (name "Net-(BT1-Pad9)") (class "Default")
      (node (ref "BT1") (pin "9") (pinfunction "9_9") (pintype "passive"))
      (node (ref "H5") (pin "2") (pinfunction "2_2") (pintype "passive"))
    )
    (net (code "38") (name "Net-(BT1-Pad11)") (class "Default")
      (node (ref "BT1") (pin "11") (pinfunction "11_11") (pintype "passive"))
      (node (ref "H5") (pin "1") (pinfunction "1_1") (pintype "passive"))
    )
    (net (code "39") (name "Net-(BT1-Pad21)") (class "Default")
      (node (ref "BT1") (pin "21") (pinfunction "21_21") (pintype "passive"))
      (node (ref "C25") (pin "2") (pinfunction "2_2") (pintype "passive"))
      (node (ref "C26") (pin "2") (pinfunction "2_2") (pintype "passive"))
      (node (ref "C27") (pin "2") (pinfunction "2_2") (pintype "passive"))
      (node (ref "C28") (pin "2") (pinfunction "2_2") (pintype "passive"))
      (node (ref "H4") (pin "1") (pinfunction "1_1") (pintype "passive"))
      (node (ref "R67") (pin "2") (pinfunction "2_2") (pintype "passive"))
    )
    (net (code "40") (name "Net-(C10-Pad1)") (class "Default")
      (node (ref "C10") (pin "1") (pinfunction "1_1") (pintype "passive"))
      (node (ref "C11") (pin "1") (pinfunction "1_1") (pintype "passive"))
      (node (ref "P1") (pin "1") (pinfunction "1_1") (pintype "passive"))
      (node (ref "R12") (pin "1") (pinfunction "1_1") (pintype "passive"))
      (node (ref "R14") (pin "1") (pinfunction "1_1") (pintype "passive"))
      (node (ref "U1") (pin "5") (pinfunction "Line_5") (pintype "passive"))
      (node (ref "U1") (pin "6") (pinfunction "Line_6") (pintype "passive"))
      (node (ref "U1") (pin "7") (pinfunction "Line_7") (pintype "passive"))
    )
    (net (code "41") (name "Net-(C10-Pad2)") (class "Default")
      (node (ref "C10") (pin "2") (pinfunction "2_2") (pintype "passive"))
      (node (ref "C11") (pin "2") (pinfunction "2_2") (pintype "passive"))
      (node (ref "C16") (pin "1") (pinfunction "1_1") (pintype "passive"))
      (node (ref "C17") (pin "1") (pinfunction "1_1") (pintype "passive"))
      (node (ref "M1") (pin "1") (pinfunction "1_1") (pintype "passive"))
    )
    (net (code "42") (name "Net-(C12-Pad1)") (class "Default")
      (node (ref "C12") (pin "1") (pinfunction "1_1") (pintype "passive"))
      (node (ref "C14") (pin "2") (pinfunction "2_2") (pintype "passive"))
      (node (ref "K4") (pin "1") (pinfunction "1_1") (pintype "passive"))
      (node (ref "L3") (pin "2") (pinfunction "2_2") (pintype "passive"))
      (node (ref "R37") (pin "2") (pinfunction "2_2") (pintype "passive"))
    )
    (net (code "43") (name "Net-(C12-Pad2)") (class "Default")
      (node (ref "C12") (pin "2") (pinfunction "2_2") (pintype "passive"))
      (node (ref "C8") (pin "1") (pinfunction "1_1") (pintype "passive"))
      (node (ref "K2") (pin "4") (pinfunction "4_4") (pintype "passive"))
      (node (ref "L3") (pin "1") (pinfunction "1_1") (pintype "passive"))
      (node (ref "R13") (pin "1") (pinfunction "1_1") (pintype "passive"))
    )
    (net (code "44") (name "Net-(C13-Pad1)") (class "Default")
      (node (ref "C13") (pin "1") (pinfunction "1_1") (pintype "passive"))
      (node (ref "C15") (pin "1") (pinfunction "1_1") (pintype "passive"))
      (node (ref "L3") (pin "3") (pinfunction "3_3") (pintype "passive"))
      (node (ref "P5") (pin "1") (pinfunction "1_1") (pintype "passive"))
      (node (ref "R27") (pin "1") (pinfunction "1_1") (pintype "passive"))
      (node (ref "RV2") (pin "1") (pinfunction "1_1") (pintype "passive"))
      (node (ref "RV3") (pin "1") (pinfunction "1_1") (pintype "passive"))
    )
    (net (code "45") (name "Net-(C13-Pad2)") (class "Default")
      (node (ref "C13") (pin "2") (pinfunction "2_2") (pintype "passive"))
      (node (ref "C7") (pin "1") (pinfunction "1_1") (pintype "passive"))
      (node (ref "L3") (pin "4") (pinfunction "4_4") (pintype "passive"))
      (node (ref "P3") (pin "1") (pinfunction "1_1") (pintype "passive"))
      (node (ref "R20") (pin "1") (pinfunction "1_1") (pintype "passive"))
      (node (ref "RV1") (pin "1") (pinfunction "1_1") (pintype "passive"))
      (node (ref "RV2") (pin "2") (pinfunction "2_2") (pintype "passive"))
    )
    (net (code "46") (name "Net-(C14-Pad1)") (class "Default")
      (node (ref "C14") (pin "1") (pinfunction "1_1") (pintype "passive"))
      (node (ref "C8") (pin "2") (pinfunction "2_2") (pintype "passive"))
      (node (ref "M2") (pin "1") (pinfunction "1_1") (pintype "passive"))
    )
    (net (code "47") (name "Net-(C15-Pad2)") (class "Default")
      (node (ref "C15") (pin "2") (pinfunction "2_2") (pintype "passive"))
      (node (ref "C7") (pin "2") (pinfunction "2_2") (pintype "passive"))
      (node (ref "M3") (pin "1") (pinfunction "1_1") (pintype "passive"))
      (node (ref "VR1") (pin "2") (pinfunction "2_2") (pintype "passive"))
    )
    (net (code "48") (name "Net-(C16-Pad2)") (class "Default")
      (node (ref "C16") (pin "2") (pinfunction "2_2") (pintype "passive"))
      (node (ref "C17") (pin "2") (pinfunction "2_2") (pintype "passive"))
      (node (ref "K5") (pin "4") (pinfunction "4_4") (pintype "passive"))
      (node (ref "P6") (pin "1") (pinfunction "1_1") (pintype "passive"))
      (node (ref "R34") (pin "1") (pinfunction "1_1") (pintype "passive"))
      (node (ref "R38") (pin "2") (pinfunction "2_2") (pintype "passive"))
    )
    (net (code "49") (name "Net-(C19-Pad2)") (class "Default")
      (node (ref "C19") (pin "2") (pinfunction "2_2") (pintype "passive"))
      (node (ref "R61") (pin "1") (pinfunction "1_1") (pintype "passive"))
      (node (ref "R62") (pin "1") (pinfunction "1_1") (pintype "passive"))
    )
    (net (code "50") (name "Net-(C24-Pad2)") (class "Default")
      (node (ref "C24") (pin "2") (pinfunction "2_2") (pintype "passive"))
      (node (ref "R65") (pin "1") (pinfunction "1_1") (pintype "passive"))
    )
    (net (code "51") (name "Net-(C32-Pad2)") (class "Default")
      (node (ref "C32") (pin "2") (pinfunction "2_2") (pintype "passive"))
      (node (ref "C33") (pin "2") (pinfunction "2_2") (pintype "passive"))
      (node (ref "C34") (pin "2") (pinfunction "2_2") (pintype "passive"))
      (node (ref "C39") (pin "1") (pinfunction "1_1") (pintype "passive"))
      (node (ref "L4") (pin "1") (pinfunction "1_1") (pintype "passive"))
      (node (ref "R68") (pin "2") (pinfunction "2_2") (pintype "passive"))
      (node (ref "T1") (pin "11") (pinfunction "11_11") (pintype "passive"))
    )
    (net (code "52") (name "Net-(C50-Pad1)") (class "Default")
      (node (ref "C50") (pin "1") (pinfunction "1_1") (pintype "passive"))
      (node (ref "R79") (pin "2") (pinfunction "2_2") (pintype "passive"))
    )
    (net (code "53") (name "Net-(C58-Pad1)") (class "Default")
      (node (ref "C58") (pin "1") (pinfunction "1_1") (pintype "passive"))
      (node (ref "R90") (pin "2") (pinfunction "2_2") (pintype "passive"))
    )
    (net (code "54") (name "Net-(C60-Pad1)") (class "Default")
      (node (ref "C60") (pin "1") (pinfunction "1_1") (pintype "passive"))
      (node (ref "R91") (pin "2") (pinfunction "2_2") (pintype "passive"))
    )
    (net (code "55") (name "Net-(C72-Pad1)") (class "Default")
      (node (ref "C72") (pin "1") (pinfunction "1_1") (pintype "passive"))
      (node (ref "R106") (pin "2") (pinfunction "2_2") (pintype "passive"))
      (node (ref "R115") (pin "2") (pinfunction "2_2") (pintype "passive"))
      (node (ref "R125") (pin "1") (pinfunction "1_1") (pintype "passive"))
    )
    (net (code "56") (name "Net-(C72-Pad2)") (class "Default")
      (node (ref "C72") (pin "2") (pinfunction "2_2") (pintype "passive"))
      (node (ref "R106") (pin "1") (pinfunction "1_1") (pintype "passive"))
      (node (ref "R146") (pin "2") (pinfunction "2_2") (pintype "passive"))
    )
    (net (code "57") (name "Net-(C75-Pad1)") (class "Default")
      (node (ref "C75") (pin "1") (pinfunction "1_1") (pintype "passive"))
      (node (ref "R115") (pin "1") (pinfunction "1_1") (pintype "passive"))
      (node (ref "R116") (pin "2") (pinfunction "2_2") (pintype "passive"))
    )
    (net (code "58") (name "Net-(C83-Pad2)") (class "Default")
      (node (ref "C83") (pin "2") (pinfunction "2_2") (pintype "passive"))
      (node (ref "C85") (pin "1") (pinfunction "1_1") (pintype "passive"))
      (node (ref "R126") (pin "2") (pinfunction "2_2") (pintype "passive"))
    )
    (net (code "59") (name "Net-(C87-Pad2)") (class "Default")
      (node (ref "C87") (pin "2") (pinfunction "2_2") (pintype "passive"))
      (node (ref "C88") (pin "2") (pinfunction "2_2") (pintype "passive"))
      (node (ref "L8") (pin "4") (pinfunction "4_4") (pintype "passive"))
      (node (ref "P9") (pin "1") (pinfunction "1_1") (pintype "passive"))
      (node (ref "R131") (pin "1") (pinfunction "1_1") (pintype "passive"))
      (node (ref "RV4") (pin "2") (pinfunction "2_2") (pintype "passive"))
    )
    (net (code "60") (name "Net-(C88-Pad1)") (class "Default")
      (node (ref "C88") (pin "1") (pinfunction "1_1") (pintype "passive"))
      (node (ref "C90") (pin "2") (pinfunction "2_2") (pintype "passive"))
      (node (ref "L8") (pin "3") (pinfunction "3_3") (pintype "passive"))
      (node (ref "P11") (pin "1") (pinfunction "1_1") (pintype "passive"))
      (node (ref "R144") (pin "1") (pinfunction "1_1") (pintype "passive"))
      (node (ref "RV4") (pin "1") (pinfunction "1_1") (pintype "passive"))
    )
    (net (code "61") (name "Net-(C89-Pad2)") (class "Default")
      (node (ref "C89") (pin "2") (pinfunction "2_2") (pintype "passive"))
      (node (ref "C91") (pin "1") (pinfunction "1_1") (pintype "passive"))
      (node (ref "L8") (pin "1") (pinfunction "1_1") (pintype "passive"))
      (node (ref "U10") (pin "10") (pinfunction "Line_10") (pintype "passive"))
      (node (ref "U10") (pin "8") (pinfunction "Line_8") (pintype "passive"))
      (node (ref "U10") (pin "9") (pinfunction "Line_9") (pintype "passive"))
    )
    (net (code "62") (name "Net-(D2-K)") (class "Default")
      (node (ref "D2") (pin "1") (pinfunction "K_1") (pintype "passive"))
      (node (ref "D5") (pin "2") (pinfunction "A_2") (pintype "passive"))
    )
    (net (code "63") (name "Net-(D3-A1)") (class "Default")
      (node (ref "D3") (pin "1") (pinfunction "A1_1") (pintype "passive"))
      (node (ref "D3") (pin "2") (pinfunction "A2_2") (pintype "passive"))
      (node (ref "D4") (pin "1") (pinfunction "A1_1") (pintype "passive"))
      (node (ref "D4") (pin "2") (pinfunction "A2_2") (pintype "passive"))
      (node (ref "K3") (pin "1") (pinfunction "1_1") (pintype "passive"))
    )
    (net (code "64") (name "Net-(D3-K)") (class "Default")
      (node (ref "D3") (pin "3") (pinfunction "K_3") (pintype "passive"))
      (node (ref "U2") (pin "10") (pinfunction "OUT7_10") (pintype "passive"))
    )
    (net (code "65") (name "Net-(D5-K)") (class "Default")
      (node (ref "C6") (pin "2") (pinfunction "2_2") (pintype "passive"))
      (node (ref "C9") (pin "2") (pinfunction "2_2") (pintype "passive"))
      (node (ref "D5") (pin "1") (pinfunction "K_1") (pintype "passive"))
      (node (ref "U2") (pin "9") (pinfunction "COM_9") (pintype "passive"))
    )
    (net (code "66") (name "Net-(D6-A)") (class "Default")
      (node (ref "BT1") (pin "23") (pinfunction "23_23") (pintype "passive"))
      (node (ref "C24") (pin "1") (pinfunction "1_1") (pintype "passive"))
      (node (ref "D6") (pin "1") (pinfunction "A_1") (pintype "passive"))
      (node (ref "D6") (pin "2") (pinfunction "NC_2") (pintype "passive"))
    )
    (net (code "67") (name "Net-(D6-K)") (class "Default")
      (node (ref "C25") (pin "1") (pinfunction "1_1") (pintype "passive"))
      (node (ref "C26") (pin "1") (pinfunction "1_1") (pintype "passive"))
      (node (ref "C27") (pin "1") (pinfunction "1_1") (pintype "passive"))
      (node (ref "C28") (pin "1") (pinfunction "1_1") (pintype "passive"))
      (node (ref "D6") (pin "3") (pinfunction "K_3") (pintype "passive"))
      (node (ref "H4") (pin "2") (pinfunction "2_2") (pintype "passive"))
      (node (ref "R65") (pin "2") (pinfunction "2_2") (pintype "passive"))
      (node (ref "R67") (pin "1") (pinfunction "1_1") (pintype "passive"))
    )
    (net (code "68") (name "Net-(D7-A)") (class "Default")
      (node (ref "C20") (pin "2") (pinfunction "2_2") (pintype "passive"))
      (node (ref "C30") (pin "2") (pinfunction "2_2") (pintype "passive"))
      (node (ref "C31") (pin "2") (pinfunction "2_2") (pintype "passive"))
      (node (ref "D7") (pin "1") (pinfunction "A_1") (pintype "passive"))
      (node (ref "H2") (pin "1") (pinfunction "1_1") (pintype "passive"))
      (node (ref "H2") (pin "2") (pinfunction "2_2") (pintype "passive"))
    )
    (net (code "69") (name "Net-(D7-K)") (class "Default")
      (node (ref "D7") (pin "2") (pinfunction "K_2") (pintype "passive"))
      (node (ref "R63") (pin "1") (pinfunction "1_1") (pintype "passive"))
    )
    (net (code "70") (name "Net-(D10-A)") (class "Default")
      (node (ref "C32") (pin "1") (pinfunction "1_1") (pintype "passive"))
      (node (ref "C33") (pin "1") (pinfunction "1_1") (pintype "passive"))
      (node (ref "C34") (pin "1") (pinfunction "1_1") (pintype "passive"))
      (node (ref "D10") (pin "1") (pinfunction "A_1") (pintype "passive"))
      (node (ref "D11") (pin "1") (pinfunction "K_1") (pintype "passive"))
      (node (ref "R61") (pin "2") (pinfunction "2_2") (pintype "passive"))
      (node (ref "R62") (pin "2") (pinfunction "2_2") (pintype "passive"))
      (node (ref "R68") (pin "1") (pinfunction "1_1") (pintype "passive"))
    )
    (net (code "71") (name "Net-(D10-K)") (class "Default")
      (node (ref "BT1") (pin "1") (pinfunction "1_1") (pintype "passive"))
      (node (ref "C29") (pin "2") (pinfunction "2_2") (pintype "passive"))
      (node (ref "C37") (pin "2") (pinfunction "2_2") (pintype "passive"))
      (node (ref "D10") (pin "2") (pinfunction "K_2") (pintype "passive"))
      (node (ref "D8") (pin "2") (pinfunction "K_2") (pintype "passive"))
      (node (ref "D9") (pin "2") (pinfunction "K_2") (pintype "passive"))
      (node (ref "R70") (pin "2") (pinfunction "2_2") (pintype "passive"))
      (node (ref "R78") (pin "2") (pinfunction "2_2") (pintype "passive"))
    )
    (net (code "72") (name "Net-(D11-A)") (class "Default")
      (node (ref "C19") (pin "1") (pinfunction "1_1") (pintype "passive"))
      (node (ref "D11") (pin "2") (pinfunction "A_2") (pintype "passive"))
      (node (ref "T1") (pin "9") (pinfunction "9_9") (pintype "passive"))
    )
    (net (code "73") (name "Net-(D12-A)") (class "Default")
      (node (ref "D12") (pin "1") (pinfunction "A_1") (pintype "passive"))
      (node (ref "Q4") (pin "2") (pinfunction "D_2") (pintype "passive"))
      (node (ref "T1") (pin "5") (pinfunction "5_5") (pintype "passive"))
    )
    (net (code "74") (name "Net-(D12-K)") (class "Default")
      (node (ref "C23") (pin "2") (pinfunction "2_2") (pintype "passive"))
      (node (ref "D12") (pin "2") (pinfunction "K_2") (pintype "passive"))
      (node (ref "R69") (pin "1") (pinfunction "1_1") (pintype "passive"))
    )
    (net (code "75") (name "Net-(D13-A)") (class "Default")
      (node (ref "BT1") (pin "3") (pinfunction "3_3") (pintype "passive"))
      (node (ref "D13") (pin "1") (pinfunction "A_1") (pintype "passive"))
      (node (ref "U6") (pin "5") (pinfunction "DRAIN_5") (pintype "passive"))
    )
    (net (code "76") (name "Net-(D13-K)") (class "Default")
      (node (ref "C29") (pin "1") (pinfunction "1_1") (pintype "passive"))
      (node (ref "D13") (pin "2") (pinfunction "K_2") (pintype "passive"))
      (node (ref "R75") (pin "1") (pinfunction "1_1") (pintype "passive"))
    )
    (net (code "77") (name "Net-(D14-A)") (class "Default")
      (node (ref "BT1") (pin "19") (pinfunction "19_19") (pintype "passive"))
      (node (ref "C50") (pin "2") (pinfunction "2_2") (pintype "passive"))
      (node (ref "D14") (pin "1") (pinfunction "A_1") (pintype "passive"))
      (node (ref "D14") (pin "2") (pinfunction "NC_2") (pintype "passive"))
    )
    (net (code "78") (name "Net-(D15-A1)") (class "Default")
      (node (ref "C64") (pin "2") (pinfunction "2_2") (pintype "passive"))
      (node (ref "D15") (pin "1") (pinfunction "A1_1") (pintype "passive"))
      (node (ref "H6") (pin "3") (pinfunction "3_3") (pintype "passive"))
      (node (ref "R96") (pin "1") (pinfunction "1_1") (pintype "passive"))
    )
    (net (code "79") (name "Net-(D15-A2)") (class "Default")
      (node (ref "C38") (pin "2") (pinfunction "2_2") (pintype "passive"))
      (node (ref "D15") (pin "2") (pinfunction "A2_2") (pintype "passive"))
      (node (ref "H3") (pin "3") (pinfunction "3_3") (pintype "passive"))
      (node (ref "R66") (pin "1") (pinfunction "1_1") (pintype "passive"))
    )
    (net (code "80") (name "Net-(D16-A1)") (class "Default")
      (node (ref "C52") (pin "2") (pinfunction "2_2") (pintype "passive"))
      (node (ref "C53") (pin "2") (pinfunction "2_2") (pintype "passive"))
      (node (ref "D16") (pin "1") (pinfunction "A1_1") (pintype "passive"))
      (node (ref "D16") (pin "2") (pinfunction "A2_2") (pintype "passive"))
      (node (ref "D17") (pin "2") (pinfunction "K_2") (pintype "passive"))
      (node (ref "R146") (pin "1") (pinfunction "1_1") (pintype "passive"))
      (node (ref "R88") (pin "1") (pinfunction "1_1") (pintype "passive"))
    )
    (net (code "81") (name "Net-(D16-K)") (class "Default")
      (node (ref "D16") (pin "3") (pinfunction "K_3") (pintype "passive"))
      (node (ref "R84") (pin "2") (pinfunction "2_2") (pintype "passive"))
    )
    (net (code "82") (name "Net-(D17-A)") (class "Default")
      (node (ref "D17") (pin "1") (pinfunction "A_1") (pintype "passive"))
      (node (ref "T1") (pin "3") (pinfunction "3_3") (pintype "passive"))
    )
    (net (code "83") (name "Net-(D18-A)") (class "Default")
      (node (ref "BT1") (pin "7") (pinfunction "7_7") (pintype "passive"))
      (node (ref "D18") (pin "1") (pinfunction "A_1") (pintype "passive"))
    )
    (net (code "84") (name "Net-(D18-K)") (class "Default")
      (node (ref "D18") (pin "2") (pinfunction "K_2") (pintype "passive"))
      (node (ref "R89") (pin "1") (pinfunction "1_1") (pintype "passive"))
    )
    (net (code "85") (name "Net-(D19-A)") (class "Default")
      (node (ref "C54") (pin "2") (pinfunction "2_2") (pintype "passive"))
      (node (ref "C55") (pin "2") (pinfunction "2_2") (pintype "passive"))
      (node (ref "D19") (pin "1") (pinfunction "A_1") (pintype "passive"))
      (node (ref "R90") (pin "1") (pinfunction "1_1") (pintype "passive"))
      (node (ref "U5") (pin "2") (pinfunction "IN_2") (pintype "power_in"))
    )
    (net (code "86") (name "Net-(D19-K)") (class "Default")
      (node (ref "BT1") (pin "15") (pinfunction "15_15") (pintype "passive"))
      (node (ref "C58") (pin "2") (pinfunction "2_2") (pintype "passive"))
      (node (ref "D19") (pin "2") (pinfunction "K_2") (pintype "passive"))
    )
    (net (code "87") (name "Net-(D20-K)") (class "Default")
      (node (ref "C51") (pin "2") (pinfunction "2_2") (pintype "passive"))
      (node (ref "D20") (pin "3") (pinfunction "K_3") (pintype "passive"))
      (node (ref "H7") (pin "2") (pinfunction "2_2") (pintype "passive"))
      (node (ref "R83") (pin "2") (pinfunction "2_2") (pintype "passive"))
      (node (ref "R84") (pin "1") (pinfunction "1_1") (pintype "passive"))
      (node (ref "R95") (pin "1") (pinfunction "1_1") (pintype "passive"))
    )
    (net (code "88") (name "Net-(D21-A)") (class "Default")
      (node (ref "BT1") (pin "13") (pinfunction "13_13") (pintype "passive"))
      (node (ref "C60") (pin "2") (pinfunction "2_2") (pintype "passive"))
      (node (ref "D21") (pin "1") (pinfunction "A_1") (pintype "passive"))
      (node (ref "D21") (pin "2") (pinfunction "NC_2") (pintype "passive"))
    )
    (net (code "89") (name "Net-(D23-A)") (class "Default")
      (node (ref "D23") (pin "1") (pinfunction "A_1") (pintype "passive"))
      (node (ref "D24") (pin "3") (pinfunction "K_3") (pintype "passive"))
    )
    (net (code "90") (name "Net-(D23-K)") (class "Default")
      (node (ref "D23") (pin "3") (pinfunction "K_3") (pintype "passive"))
      (node (ref "R127") (pin "1") (pinfunction "1_1") (pintype "passive"))
    )
    (net (code "91") (name "Net-(D24-A)") (class "Default")
      (node (ref "C93") (pin "1") (pinfunction "1_1") (pintype "passive"))
      (node (ref "D24") (pin "1") (pinfunction "A_1") (pintype "passive"))
      (node (ref "Q7") (pin "1") (pinfunction "B_1") (pintype "passive"))
      (node (ref "R145") (pin "1") (pinfunction "1_1") (pintype "passive"))
    )
    (net (code "92") (name "Net-(D25-A)") (class "Default")
      (node (ref "C92") (pin "2") (pinfunction "2_2") (pintype "passive"))
      (node (ref "D25") (pin "3") (pinfunction "A_3") (pintype "passive"))
      (node (ref "R136") (pin "2") (pinfunction "2_2") (pintype "passive"))
    )
    (net (code "93") (name "Net-(K1-Pad1)") (class "Default")
      (node (ref "K1") (pin "1") (pinfunction "1_1") (pintype "passive"))
      (node (ref "K2") (pin "1") (pinfunction "1_1") (pintype "passive"))
      (node (ref "L2") (pin "4") (pinfunction "4_4") (pintype "passive"))
    )
    (net (code "94") (name "Net-(K1-Pad4)") (class "Default")
      (node (ref "K1") (pin "4") (pinfunction "4_4") (pintype "passive"))
      (node (ref "U1") (pin "10") (pinfunction "Line_10") (pintype "passive"))
      (node (ref "U1") (pin "8") (pinfunction "Line_8") (pintype "passive"))
      (node (ref "U1") (pin "9") (pinfunction "Line_9") (pintype "passive"))
    )
    (net (code "95") (name "Net-(K3-Pad4)") (class "Default")
      (node (ref "K3") (pin "4") (pinfunction "4_4") (pintype "passive"))
      (node (ref "K3") (pin "9") (pinfunction "9_9") (pintype "passive"))
    )
    (net (code "96") (name "Net-(K3-Pad5)") (class "Default")
      (node (ref "K3") (pin "5") (pinfunction "5_5") (pintype "passive"))
      (node (ref "R43") (pin "2") (pinfunction "2_2") (pintype "passive"))
      (node (ref "R45") (pin "1") (pinfunction "1_1") (pintype "passive"))
      (node (ref "R46") (pin "1") (pinfunction "1_1") (pintype "passive"))
    )
    (net (code "97") (name "Net-(K3-Pad12)") (class "Default")
      (node (ref "K3") (pin "12") (pinfunction "12_12") (pintype "passive"))
      (node (ref "R8") (pin "2") (pinfunction "2_2") (pintype "passive"))
    )
    (net (code "98") (name "Net-(K4-Pad4)") (class "Default")
      (node (ref "K4") (pin "4") (pinfunction "4_4") (pintype "passive"))
      (node (ref "K5") (pin "1") (pinfunction "1_1") (pintype "passive"))
      (node (ref "L2") (pin "3") (pinfunction "3_3") (pintype "passive"))
    )
    (net (code "99") (name "Net-(L2-Pad1)") (class "Default")
      (node (ref "L2") (pin "1") (pinfunction "1_1") (pintype "passive"))
      (node (ref "P2") (pin "1") (pinfunction "1_1") (pintype "passive"))
    )
    (net (code "100") (name "Net-(L2-Pad2)") (class "Default")
      (node (ref "L2") (pin "2") (pinfunction "2_2") (pintype "passive"))
      (node (ref "P4") (pin "1") (pinfunction "1_1") (pintype "passive"))
    )
    (net (code "101") (name "Net-(LED1-Pad1)") (class "Default")
      (node (ref "LED1") (pin "1") (pinfunction "1_1") (pintype "passive"))
      (node (ref "R77") (pin "1") (pinfunction "1_1") (pintype "passive"))
    )
    (net (code "102") (name "Net-(M4-Pad1)") (class "Default")
      (node (ref "M4") (pin "1") (pinfunction "1_1") (pintype "passive"))
      (node (ref "R59") (pin "1") (pinfunction "1_1") (pintype "passive"))
      (node (ref "R60") (pin "2") (pinfunction "2_2") (pintype "passive"))
    )
    (net (code "103") (name "Net-(P10-Pad1)") (class "Default")
      (node (ref "P10") (pin "1") (pinfunction "1_1") (pintype "passive"))
      (node (ref "R135") (pin "1") (pinfunction "1_1") (pintype "passive"))
      (node (ref "U10") (pin "5") (pinfunction "Line_5") (pintype "passive"))
      (node (ref "U10") (pin "6") (pinfunction "Line_6") (pintype "passive"))
      (node (ref "U10") (pin "7") (pinfunction "Line_7") (pintype "passive"))
    )
    (net (code "104") (name "Net-(Q1-B)") (class "Default")
      (node (ref "Q1") (pin "1") (pinfunction "B_1") (pintype "passive"))
      (node (ref "R2") (pin "1") (pinfunction "1_1") (pintype "passive"))
      (node (ref "R5") (pin "2") (pinfunction "2_2") (pintype "passive"))
    )
    (net (code "105") (name "Net-(Q1-E)") (class "Default")
      (node (ref "C1") (pin "1") (pinfunction "1_1") (pintype "passive"))
      (node (ref "L1") (pin "2") (pinfunction "2_2") (pintype "passive"))
      (node (ref "Q1") (pin "3") (pinfunction "E_3") (pintype "passive"))
      (node (ref "R1") (pin "2") (pinfunction "2_2") (pintype "passive"))
    )
    (net (code "106") (name "Net-(Q2-B)") (class "Default")
      (node (ref "Q2") (pin "1") (pinfunction "B_1") (pintype "passive"))
      (node (ref "R6") (pin "2") (pinfunction "2_2") (pintype "passive"))
    )
    (net (code "107") (name "Net-(Q2-C)") (class "Default")
      (node (ref "Q2") (pin "2") (pinfunction "C_2") (pintype "passive"))
      (node (ref "R1") (pin "1") (pinfunction "1_1") (pintype "passive"))
      (node (ref "R2") (pin "2") (pinfunction "2_2") (pintype "passive"))
      (node (ref "R5") (pin "1") (pinfunction "1_1") (pintype "passive"))
    )
    (net (code "108") (name "Net-(Q3-B)") (class "Default")
      (node (ref "Q3") (pin "1") (pinfunction "B_1") (pintype "passive"))
      (node (ref "R80") (pin "2") (pinfunction "2_2") (pintype "passive"))
    )
    (net (code "109") (name "Net-(Q3-C)") (class "Default")
      (node (ref "H3") (pin "1") (pinfunction "1_1") (pintype "passive"))
      (node (ref "Q3") (pin "2") (pinfunction "C_2") (pintype "passive"))
      (node (ref "R76") (pin "1") (pinfunction "1_1") (pintype "passive"))
    )
    (net (code "110") (name "Net-(Q4-G)") (class "Default")
      (node (ref "Q4") (pin "1") (pinfunction "G_1") (pintype "passive"))
      (node (ref "R103") (pin "1") (pinfunction "1_1") (pintype "passive"))
      (node (ref "R108") (pin "1") (pinfunction "1_1") (pintype "passive"))
    )
    (net (code "111") (name "Net-(Q4-S)") (class "Default")
      (node (ref "Q4") (pin "3") (pinfunction "S_3") (pintype "passive"))
      (node (ref "R109") (pin "1") (pinfunction "1_1") (pintype "passive"))
      (node (ref "R117") (pin "1") (pinfunction "1_1") (pintype "passive"))
      (node (ref "R118") (pin "1") (pinfunction "1_1") (pintype "passive"))
      (node (ref "R119") (pin "1") (pinfunction "1_1") (pintype "passive"))
      (node (ref "R120") (pin "1") (pinfunction "1_1") (pintype "passive"))
    )
    (net (code "112") (name "Net-(Q5-B)") (class "Default")
      (node (ref "Q5") (pin "1") (pinfunction "B_1") (pintype "passive"))
      (node (ref "R113") (pin "2") (pinfunction "2_2") (pintype "passive"))
    )
    (net (code "113") (name "Net-(Q5-C)") (class "Default")
      (node (ref "H6") (pin "1") (pinfunction "1_1") (pintype "passive"))
      (node (ref "Q5") (pin "2") (pinfunction "C_2") (pintype "passive"))
      (node (ref "R102") (pin "1") (pinfunction "1_1") (pintype "passive"))
    )
    (net (code "114") (name "Net-(Q6-B)") (class "Default")
      (node (ref "Q6") (pin "1") (pinfunction "B_1") (pintype "passive"))
      (node (ref "Q7") (pin "2") (pinfunction "C_2") (pintype "passive"))
      (node (ref "R130") (pin "2") (pinfunction "2_2") (pintype "passive"))
    )
    (net (code "115") (name "Net-(Q6-C)") (class "Default")
      (node (ref "C74") (pin "1") (pinfunction "1_1") (pintype "passive"))
      (node (ref "C75") (pin "2") (pinfunction "2_2") (pintype "passive"))
      (node (ref "D25") (pin "1") (pinfunction "C_1") (pintype "passive"))
      (node (ref "Q6") (pin "2") (pinfunction "C_2") (pintype "passive"))
      (node (ref "U7") (pin "1") (pinfunction "COMP_1") (pintype "input"))
    )
    (net (code "116") (name "Net-(R10-Pad1)") (class "Default")
      (node (ref "R10") (pin "1") (pinfunction "1_1") (pintype "passive"))
      (node (ref "R11") (pin "2") (pinfunction "2_2") (pintype "passive"))
    )
    (net (code "117") (name "Net-(R10-Pad2)") (class "Default")
      (node (ref "R10") (pin "2") (pinfunction "2_2") (pintype "passive"))
      (node (ref "R9") (pin "1") (pinfunction "1_1") (pintype "passive"))
    )
    (net (code "118") (name "Net-(R11-Pad1)") (class "Default")
      (node (ref "R11") (pin "1") (pinfunction "1_1") (pintype "passive"))
      (node (ref "R12") (pin "2") (pinfunction "2_2") (pintype "passive"))
    )
    (net (code "119") (name "Net-(R13-Pad2)") (class "Default")
      (node (ref "R13") (pin "2") (pinfunction "2_2") (pintype "passive"))
      (node (ref "R16") (pin "1") (pinfunction "1_1") (pintype "passive"))
    )
    (net (code "120") (name "Net-(R14-Pad2)") (class "Default")
      (node (ref "R14") (pin "2") (pinfunction "2_2") (pintype "passive"))
      (node (ref "R17") (pin "1") (pinfunction "1_1") (pintype "passive"))
    )
    (net (code "121") (name "Net-(R16-Pad2)") (class "Default")
      (node (ref "R16") (pin "2") (pinfunction "2_2") (pintype "passive"))
      (node (ref "R25") (pin "1") (pinfunction "1_1") (pintype "passive"))
    )
    (net (code "122") (name "Net-(R17-Pad2)") (class "Default")
      (node (ref "R17") (pin "2") (pinfunction "2_2") (pintype "passive"))
      (node (ref "R26") (pin "1") (pinfunction "1_1") (pintype "passive"))
    )
    (net (code "123") (name "Net-(R20-Pad2)") (class "Default")
      (node (ref "R20") (pin "2") (pinfunction "2_2") (pintype "passive"))
      (node (ref "R21") (pin "1") (pinfunction "1_1") (pintype "passive"))
    )
    (net (code "124") (name "Net-(R21-Pad2)") (class "Default")
      (node (ref "R21") (pin "2") (pinfunction "2_2") (pintype "passive"))
      (node (ref "R22") (pin "1") (pinfunction "1_1") (pintype "passive"))
    )
    (net (code "125") (name "Net-(R22-Pad2)") (class "Default")
      (node (ref "R22") (pin "2") (pinfunction "2_2") (pintype "passive"))
      (node (ref "R23") (pin "1") (pinfunction "1_1") (pintype "passive"))
    )
    (net (code "126") (name "Net-(R25-Pad2)") (class "Default")
      (node (ref "R25") (pin "2") (pinfunction "2_2") (pintype "passive"))
      (node (ref "R37") (pin "1") (pinfunction "1_1") (pintype "passive"))
    )
    (net (code "127") (name "Net-(R26-Pad2)") (class "Default")
      (node (ref "R26") (pin "2") (pinfunction "2_2") (pintype "passive"))
      (node (ref "R38") (pin "1") (pinfunction "1_1") (pintype "passive"))
    )
    (net (code "128") (name "Net-(R27-Pad2)") (class "Default")
      (node (ref "R27") (pin "2") (pinfunction "2_2") (pintype "passive"))
      (node (ref "R28") (pin "1") (pinfunction "1_1") (pintype "passive"))
    )
    (net (code "129") (name "Net-(R28-Pad2)") (class "Default")
      (node (ref "R28") (pin "2") (pinfunction "2_2") (pintype "passive"))
      (node (ref "R29") (pin "1") (pinfunction "1_1") (pintype "passive"))
    )
    (net (code "130") (name "Net-(R29-Pad2)") (class "Default")
      (node (ref "R29") (pin "2") (pinfunction "2_2") (pintype "passive"))
      (node (ref "R30") (pin "1") (pinfunction "1_1") (pintype "passive"))
    )
    (net (code "131") (name "Net-(R31-Pad1)") (class "Default")
      (node (ref "R31") (pin "1") (pinfunction "1_1") (pintype "passive"))
      (node (ref "R32") (pin "2") (pinfunction "2_2") (pintype "passive"))
    )
    (net (code "132") (name "Net-(R32-Pad1)") (class "Default")
      (node (ref "R32") (pin "1") (pinfunction "1_1") (pintype "passive"))
      (node (ref "R33") (pin "2") (pinfunction "2_2") (pintype "passive"))
    )
    (net (code "133") (name "Net-(R33-Pad1)") (class "Default")
      (node (ref "R33") (pin "1") (pinfunction "1_1") (pintype "passive"))
      (node (ref "R34") (pin "2") (pinfunction "2_2") (pintype "passive"))
    )
    (net (code "134") (name "Net-(R40-Pad2)") (class "Default")
      (node (ref "R40") (pin "2") (pinfunction "2_2") (pintype "passive"))
      (node (ref "R41") (pin "1") (pinfunction "1_1") (pintype "passive"))
    )
    (net (code "135") (name "Net-(R41-Pad2)") (class "Default")
      (node (ref "R41") (pin "2") (pinfunction "2_2") (pintype "passive"))
      (node (ref "R42") (pin "1") (pinfunction "1_1") (pintype "passive"))
    )
    (net (code "136") (name "Net-(R42-Pad2)") (class "Default")
      (node (ref "R42") (pin "2") (pinfunction "2_2") (pintype "passive"))
      (node (ref "R43") (pin "1") (pinfunction "1_1") (pintype "passive"))
    )
    (net (code "137") (name "Net-(R45-Pad2)") (class "Default")
      (node (ref "R45") (pin "2") (pinfunction "2_2") (pintype "passive"))
      (node (ref "R49") (pin "1") (pinfunction "1_1") (pintype "passive"))
    )
    (net (code "138") (name "Net-(R46-Pad2)") (class "Default")
      (node (ref "R46") (pin "2") (pinfunction "2_2") (pintype "passive"))
      (node (ref "R50") (pin "1") (pinfunction "1_1") (pintype "passive"))
    )
    (net (code "139") (name "Net-(R49-Pad2)") (class "Default")
      (node (ref "R49") (pin "2") (pinfunction "2_2") (pintype "passive"))
      (node (ref "R54") (pin "1") (pinfunction "1_1") (pintype "passive"))
    )
    (net (code "140") (name "Net-(R50-Pad2)") (class "Default")
      (node (ref "R50") (pin "2") (pinfunction "2_2") (pintype "passive"))
      (node (ref "R55") (pin "1") (pinfunction "1_1") (pintype "passive"))
    )
    (net (code "141") (name "Net-(R52-Pad1)") (class "Default")
      (node (ref "R52") (pin "1") (pinfunction "1_1") (pintype "passive"))
      (node (ref "R56") (pin "2") (pinfunction "2_2") (pintype "passive"))
    )
    (net (code "142") (name "Net-(R54-Pad2)") (class "Default")
      (node (ref "R54") (pin "2") (pinfunction "2_2") (pintype "passive"))
      (node (ref "R57") (pin "1") (pinfunction "1_1") (pintype "passive"))
    )
    (net (code "143") (name "Net-(R55-Pad2)") (class "Default")
      (node (ref "R55") (pin "2") (pinfunction "2_2") (pintype "passive"))
      (node (ref "R58") (pin "1") (pinfunction "1_1") (pintype "passive"))
    )
    (net (code "144") (name "Net-(R56-Pad1)") (class "Default")
      (node (ref "R56") (pin "1") (pinfunction "1_1") (pintype "passive"))
      (node (ref "R59") (pin "2") (pinfunction "2_2") (pintype "passive"))
    )
    (net (code "145") (name "Net-(R57-Pad2)") (class "Default")
      (node (ref "R57") (pin "2") (pinfunction "2_2") (pintype "passive"))
      (node (ref "R60") (pin "1") (pinfunction "1_1") (pintype "passive"))
    )
    (net (code "146") (name "Net-(R64-Pad2)") (class "Default")
      (node (ref "R64") (pin "2") (pinfunction "2_2") (pintype "passive"))
      (node (ref "R69") (pin "2") (pinfunction "2_2") (pintype "passive"))
    )
    (net (code "147") (name "Net-(R70-Pad1)") (class "Default")
      (node (ref "R70") (pin "1") (pinfunction "1_1") (pintype "passive"))
      (node (ref "R73") (pin "2") (pinfunction "2_2") (pintype "passive"))
    )
    (net (code "148") (name "Net-(R71-Pad1)") (class "Default")
      (node (ref "R71") (pin "1") (pinfunction "1_1") (pintype "passive"))
      (node (ref "R74") (pin "2") (pinfunction "2_2") (pintype "passive"))
    )
    (net (code "149") (name "Net-(R71-Pad2)") (class "Default")
      (node (ref "R71") (pin "2") (pinfunction "2_2") (pintype "passive"))
      (node (ref "R73") (pin "1") (pinfunction "1_1") (pintype "passive"))
    )
    (net (code "150") (name "Net-(R72-Pad1)") (class "Default")
      (node (ref "R72") (pin "1") (pinfunction "1_1") (pintype "passive"))
      (node (ref "R75") (pin "2") (pinfunction "2_2") (pintype "passive"))
    )
    (net (code "151") (name "Net-(R72-Pad2)") (class "Default")
      (node (ref "R72") (pin "2") (pinfunction "2_2") (pintype "passive"))
      (node (ref "R74") (pin "1") (pinfunction "1_1") (pintype "passive"))
    )
    (net (code "152") (name "Net-(R78-Pad1)") (class "Default")
      (node (ref "R78") (pin "1") (pinfunction "1_1") (pintype "passive"))
      (node (ref "R81") (pin "2") (pinfunction "2_2") (pintype "passive"))
    )
    (net (code "153") (name "Net-(R81-Pad1)") (class "Default")
      (node (ref "R81") (pin "1") (pinfunction "1_1") (pintype "passive"))
      (node (ref "R86") (pin "2") (pinfunction "2_2") (pintype "passive"))
    )
    (net (code "154") (name "Net-(R82-Pad2)") (class "Default")
      (node (ref "R82") (pin "2") (pinfunction "2_2") (pintype "passive"))
      (node (ref "R83") (pin "1") (pinfunction "1_1") (pintype "passive"))
    )
    (net (code "155") (name "Net-(R100-Pad1)") (class "Default")
      (node (ref "R100") (pin "1") (pinfunction "1_1") (pintype "passive"))
      (node (ref "R101") (pin "2") (pinfunction "2_2") (pintype "passive"))
    )
    (net (code "156") (name "Net-(R104-Pad2)") (class "Default")
      (node (ref "R104") (pin "2") (pinfunction "2_2") (pintype "passive"))
      (node (ref "R105") (pin "2") (pinfunction "2_2") (pintype "passive"))
    )
    (net (code "157") (name "Net-(R110-Pad2)") (class "Default")
      (node (ref "R110") (pin "2") (pinfunction "2_2") (pintype "passive"))
      (node (ref "R111") (pin "1") (pinfunction "1_1") (pintype "passive"))
    )
    (net (code "158") (name "Net-(R114-Pad2)") (class "Default")
      (node (ref "R114") (pin "2") (pinfunction "2_2") (pintype "passive"))
      (node (ref "U8") (pin "1") (pinfunction "1_1") (pintype "passive"))
    )
    (net (code "159") (name "Net-(R122-Pad2)") (class "Default")
      (node (ref "R122") (pin "2") (pinfunction "2_2") (pintype "passive"))
      (node (ref "U8") (pin "4") (pinfunction "4_4") (pintype "passive"))
    )
    (net (code "160") (name "Net-(R131-Pad2)") (class "Default")
      (node (ref "R131") (pin "2") (pinfunction "2_2") (pintype "passive"))
      (node (ref "R137") (pin "2") (pinfunction "2_2") (pintype "passive"))
    )
    (net (code "161") (name "Net-(R132-Pad2)") (class "Default")
      (node (ref "R132") (pin "2") (pinfunction "2_2") (pintype "passive"))
      (node (ref "R133") (pin "2") (pinfunction "2_2") (pintype "passive"))
    )
    (net (code "162") (name "Net-(R133-Pad1)") (class "Default")
      (node (ref "R133") (pin "1") (pinfunction "1_1") (pintype "passive"))
      (node (ref "R134") (pin "1") (pinfunction "1_1") (pintype "passive"))
    )
    (net (code "163") (name "Net-(R134-Pad2)") (class "Default")
      (node (ref "R134") (pin "2") (pinfunction "2_2") (pintype "passive"))
      (node (ref "R135") (pin "2") (pinfunction "2_2") (pintype "passive"))
    )
    (net (code "164") (name "Net-(R137-Pad1)") (class "Default")
      (node (ref "R137") (pin "1") (pinfunction "1_1") (pintype "passive"))
      (node (ref "R138") (pin "1") (pinfunction "1_1") (pintype "passive"))
    )
    (net (code "165") (name "Net-(R138-Pad2)") (class "Default")
      (node (ref "R138") (pin "2") (pinfunction "2_2") (pintype "passive"))
      (node (ref "R144") (pin "2") (pinfunction "2_2") (pintype "passive"))
    )
    (net (code "166") (name "Net-(R139-Pad2)") (class "Default")
      (node (ref "R139") (pin "2") (pinfunction "2_2") (pintype "passive"))
      (node (ref "R140") (pin "2") (pinfunction "2_2") (pintype "passive"))
    )
    (net (code "167") (name "Net-(R140-Pad1)") (class "Default")
      (node (ref "R140") (pin "1") (pinfunction "1_1") (pintype "passive"))
      (node (ref "R141") (pin "1") (pinfunction "1_1") (pintype "passive"))
    )
    (net (code "168") (name "Net-(R141-Pad2)") (class "Default")
      (node (ref "R141") (pin "2") (pinfunction "2_2") (pintype "passive"))
      (node (ref "R142") (pin "2") (pinfunction "2_2") (pintype "passive"))
    )
    (net (code "169") (name "Net-(RV1-Pad2)") (class "Default")
      (node (ref "RV1") (pin "2") (pinfunction "2_2") (pintype "passive"))
      (node (ref "RV3") (pin "2") (pinfunction "2_2") (pintype "passive"))
      (node (ref "VR1") (pin "1") (pinfunction "1_1") (pintype "passive"))
    )
    (net (code "170") (name "Net-(U1-Vfef)") (class "Default")
      (node (ref "R4") (pin "2") (pinfunction "2_2") (pintype "passive"))
      (node (ref "U1") (pin "1") (pinfunction "Vfef_1") (pintype "passive"))
    )
    (net (code "171") (name "Net-(U1-Vout)") (class "Default")
      (node (ref "R3") (pin "2") (pinfunction "2_2") (pintype "passive"))
      (node (ref "U1") (pin "2") (pinfunction "Vout_2") (pintype "passive"))
    )
    (net (code "172") (name "Net-(U2-IN1)") (class "Default")
      (node (ref "R15") (pin "1") (pinfunction "1_1") (pintype "passive"))
      (node (ref "U2") (pin "1") (pinfunction "IN1_1") (pintype "passive"))
    )
    (net (code "173") (name "Net-(U2-IN2)") (class "Default")
      (node (ref "R19") (pin "1") (pinfunction "1_1") (pintype "passive"))
      (node (ref "U2") (pin "2") (pinfunction "IN2_2") (pintype "passive"))
    )
    (net (code "174") (name "Net-(U2-IN3)") (class "Default")
      (node (ref "R24") (pin "1") (pinfunction "1_1") (pintype "passive"))
      (node (ref "U2") (pin "3") (pinfunction "IN3_3") (pintype "passive"))
    )
    (net (code "175") (name "Net-(U2-IN4)") (class "Default")
      (node (ref "R36") (pin "1") (pinfunction "1_1") (pintype "passive"))
      (node (ref "U2") (pin "4") (pinfunction "IN4_4") (pintype "passive"))
    )
    (net (code "176") (name "Net-(U2-IN5)") (class "Default")
      (node (ref "R39") (pin "1") (pinfunction "1_1") (pintype "passive"))
      (node (ref "U2") (pin "5") (pinfunction "IN5_5") (pintype "passive"))
    )
    (net (code "177") (name "Net-(U2-IN6)") (class "Default")
      (node (ref "R47") (pin "1") (pinfunction "1_1") (pintype "passive"))
      (node (ref "U2") (pin "6") (pinfunction "IN6_6") (pintype "passive"))
    )
    (net (code "178") (name "Net-(U2-IN7)") (class "Default")
      (node (ref "R51") (pin "1") (pinfunction "1_1") (pintype "passive"))
      (node (ref "U2") (pin "7") (pinfunction "IN7_7") (pintype "passive"))
    )
    (net (code "179") (name "Net-(U4A-1_IN-)") (class "Default")
      (node (ref "U4") (pin "1") (pinfunction "1_OUT_1") (pintype "output"))
      (node (ref "U4") (pin "2") (pinfunction "1_IN-_2") (pintype "input"))
    )
    (net (code "180") (name "Net-(U4B-2_IN+)") (class "Default")
      (node (ref "C78") (pin "1") (pinfunction "1_1") (pintype "passive"))
      (node (ref "R111") (pin "2") (pinfunction "2_2") (pintype "passive"))
      (node (ref "R121") (pin "1") (pinfunction "1_1") (pintype "passive"))
      (node (ref "U4") (pin "5") (pinfunction "2_IN+_5") (pintype "input"))
    )
    (net (code "181") (name "Net-(U4B-2_IN-)") (class "Default")
      (node (ref "C71") (pin "2") (pinfunction "2_2") (pintype "passive"))
      (node (ref "R105") (pin "1") (pinfunction "1_1") (pintype "passive"))
      (node (ref "R99") (pin "2") (pinfunction "2_2") (pintype "passive"))
      (node (ref "U4") (pin "6") (pinfunction "2_IN-_6") (pintype "input"))
    )
    (net (code "182") (name "Net-(U4B-2_OUT)") (class "Default")
      (node (ref "C71") (pin "1") (pinfunction "1_1") (pintype "passive"))
      (node (ref "R107") (pin "2") (pinfunction "2_2") (pintype "passive"))
      (node (ref "R99") (pin "1") (pinfunction "1_1") (pintype "passive"))
      (node (ref "U4") (pin "7") (pinfunction "2_OUT_7") (pintype "output"))
    )
    (net (code "183") (name "Net-(U4C-3_IN-)") (class "Default")
      (node (ref "U4") (pin "8") (pinfunction "3_OUT_8") (pintype "output"))
      (node (ref "U4") (pin "9") (pinfunction "3_IN-_9") (pintype "input"))
    )
    (net (code "184") (name "Net-(U4D-4_IN-)") (class "Default")
      (node (ref "U4") (pin "13") (pinfunction "4_IN-_13") (pintype "input"))
      (node (ref "U4") (pin "14") (pinfunction "4_OUT_14") (pintype "output"))
    )
    (net (code "185") (name "Net-(U6-BBA)") (class "Default")
      (node (ref "C61") (pin "2") (pinfunction "2_2") (pintype "passive"))
      (node (ref "R86") (pin "1") (pinfunction "1_1") (pintype "passive"))
      (node (ref "R97") (pin "2") (pinfunction "2_2") (pintype "passive"))
      (node (ref "U6") (pin "1") (pinfunction "BBA_1") (pintype "passive"))
    )
    (net (code "186") (name "Net-(U6-CS)") (class "Default")
      (node (ref "R93") (pin "1") (pinfunction "1_1") (pintype "passive"))
      (node (ref "R94") (pin "1") (pinfunction "1_1") (pintype "passive"))
      (node (ref "U6") (pin "3") (pinfunction "CS_3") (pintype "passive"))
    )
    (net (code "187") (name "Net-(U6-FBB)") (class "Default")
      (node (ref "C81") (pin "2") (pinfunction "2_2") (pintype "passive"))
      (node (ref "R122") (pin "1") (pinfunction "1_1") (pintype "passive"))
      (node (ref "U6") (pin "2") (pinfunction "FBB_2") (pintype "passive"))
    )
    (net (code "188") (name "Net-(U6-VCC)") (class "Default")
      (node (ref "C59") (pin "1") (pinfunction "1_1") (pintype "passive"))
      (node (ref "C62") (pin "1") (pinfunction "1_1") (pintype "passive"))
      (node (ref "C63") (pin "1") (pinfunction "1_1") (pintype "passive"))
      (node (ref "R89") (pin "2") (pinfunction "2_2") (pintype "passive"))
      (node (ref "U6") (pin "7") (pinfunction "VCC_7") (pintype "power_in"))
    )
    (net (code "189") (name "Net-(U7-CURRENT_SENSE)") (class "Default")
      (node (ref "C77") (pin "2") (pinfunction "2_2") (pintype "passive"))
      (node (ref "C84") (pin "1") (pinfunction "1_1") (pintype "passive"))
      (node (ref "R109") (pin "2") (pinfunction "2_2") (pintype "passive"))
      (node (ref "U7") (pin "3") (pinfunction "CURRENT_SENSE_3") (pintype "input"))
    )
    (net (code "190") (name "Net-(U7-OUT)") (class "Default")
      (node (ref "D22") (pin "1") (pinfunction "C_1") (pintype "passive"))
      (node (ref "D22") (pin "2") (pinfunction "C_2") (pintype "passive"))
      (node (ref "R103") (pin "2") (pinfunction "2_2") (pintype "passive"))
      (node (ref "U7") (pin "6") (pinfunction "OUT_6") (pintype "output"))
    )
    (net (code "191") (name "Net-(U7-RT{slash}CT)") (class "Default")
      (node (ref "C80") (pin "2") (pinfunction "2_2") (pintype "passive"))
      (node (ref "C84") (pin "2") (pinfunction "2_2") (pintype "passive"))
      (node (ref "R112") (pin "1") (pinfunction "1_1") (pintype "passive"))
      (node (ref "U7") (pin "4") (pinfunction "RT/CT_4") (pintype "input"))
    )
    (net (code "192") (name "Net-(U7-VCC)") (class "Default")
      (node (ref "C66") (pin "1") (pinfunction "1_1") (pintype "passive"))
      (node (ref "C73") (pin "2") (pinfunction "2_2") (pintype "passive"))
      (node (ref "H7") (pin "1") (pinfunction "1_1") (pintype "passive"))
      (node (ref "R95") (pin "2") (pinfunction "2_2") (pintype "passive"))
      (node (ref "U7") (pin "7") (pinfunction "VCC_7") (pintype "power_in"))
    )
    (net (code "193") (name "Net-(U7-VOLTAGE_FB)") (class "Default")
      (node (ref "C74") (pin "2") (pinfunction "2_2") (pintype "passive"))
      (node (ref "R116") (pin "1") (pinfunction "1_1") (pintype "passive"))
      (node (ref "U7") (pin "2") (pinfunction "VOLTAGE_FB_2") (pintype "input"))
    )
    (net (code "194") (name "Net-(U7-VREF)") (class "Default")
      (node (ref "C79") (pin "2") (pinfunction "2_2") (pintype "passive"))
      (node (ref "D25") (pin "2") (pinfunction "C_2") (pintype "passive"))
      (node (ref "R112") (pin "2") (pinfunction "2_2") (pintype "passive"))
      (node (ref "R136") (pin "1") (pinfunction "1_1") (pintype "passive"))
      (node (ref "U7") (pin "8") (pinfunction "VREF_8") (pintype "output"))
    )
    (net (code "195") (name "Net-(U9-K)") (class "Default")
      (node (ref "C83") (pin "1") (pinfunction "1_1") (pintype "passive"))
      (node (ref "R123") (pin "2") (pinfunction "2_2") (pintype "passive"))
      (node (ref "R126") (pin "1") (pinfunction "1_1") (pintype "passive"))
      (node (ref "U8") (pin "2") (pinfunction "2_2") (pintype "passive"))
      (node (ref "U9") (pin "1") (pinfunction "K_1") (pintype "passive"))
    )
    (net (code "196") (name "Net-(U9-R)") (class "Default")
      (node (ref "C85") (pin "2") (pinfunction "2_2") (pintype "passive"))
      (node (ref "R101") (pin "1") (pinfunction "1_1") (pintype "passive"))
      (node (ref "R128") (pin "2") (pinfunction "2_2") (pintype "passive"))
      (node (ref "R129") (pin "2") (pinfunction "2_2") (pintype "passive"))
      (node (ref "R98") (pin "2") (pinfunction "2_2") (pintype "passive"))
      (node (ref "U9") (pin "8") (pinfunction "R_8") (pintype "passive"))
    )
    (net (code "197") (name "Net-(U10-Vfef)") (class "Default")
      (node (ref "R104") (pin "1") (pinfunction "1_1") (pintype "passive"))
      (node (ref "U10") (pin "1") (pinfunction "Vfef_1") (pintype "passive"))
    )
    (net (code "198") (name "Net-(U10-Vout)") (class "Default")
      (node (ref "R110") (pin "1") (pinfunction "1_1") (pintype "passive"))
      (node (ref "U10") (pin "2") (pinfunction "Vout_2") (pintype "passive"))
    )
    (net (code "199") (name "unconnected-(D9-A-Pad1)") (class "Default")
      (node (ref "D9") (pin "1") (pinfunction "A_1") (pintype "passive+no_connect"))
    )
    (net (code "200") (name "unconnected-(D20-NC-Pad2)") (class "Default")
      (node (ref "D20") (pin "2") (pinfunction "NC_2") (pintype "passive+no_connect"))
    )
    (net (code "201") (name "unconnected-(D23-NC-Pad2)") (class "Default")
      (node (ref "D23") (pin "2") (pinfunction "NC_2") (pintype "passive+no_connect"))
    )
    (net (code "202") (name "unconnected-(D24-NC-Pad2)") (class "Default")
      (node (ref "D24") (pin "2") (pinfunction "NC_2") (pintype "passive+no_connect"))
    )
    (net (code "203") (name "unconnected-(H8-Pad3)") (class "Default")
      (node (ref "H8") (pin "3") (pinfunction "3_3") (pintype "passive"))
    )
    (net (code "204") (name "unconnected-(H8-Pad20)") (class "Default")
      (node (ref "H8") (pin "20") (pinfunction "20_20") (pintype "passive+no_connect"))
    )
    (net (code "205") (name "unconnected-(H8-Pad21)") (class "Default")
      (node (ref "H8") (pin "21") (pinfunction "21_21") (pintype "passive+no_connect"))
    )
    (net (code "206") (name "unconnected-(H8-Pad29)") (class "Default")
      (node (ref "H8") (pin "29") (pinfunction "29_29") (pintype "passive+no_connect"))
    )
    (net (code "207") (name "unconnected-(H8-Pad30)") (class "Default")
      (node (ref "H8") (pin "30") (pinfunction "30_30") (pintype "passive+no_connect"))
    )
    (net (code "208") (name "unconnected-(K3-Pad3)") (class "Default")
      (node (ref "K3") (pin "3") (pinfunction "3_3") (pintype "passive+no_connect"))
    )
    (net (code "209") (name "unconnected-(K3-Pad10)") (class "Default")
      (node (ref "K3") (pin "10") (pinfunction "10_10") (pintype "passive+no_connect"))
    )
    (net (code "210") (name "unconnected-(U6-NC-Pad4)") (class "Default")
      (node (ref "U6") (pin "4") (pinfunction "NC_4") (pintype "passive+no_connect"))
    )
    (net (code "211") (name "unconnected-(U9-NC-Pad4)") (class "Default")
      (node (ref "U9") (pin "4") (pinfunction "NC_4") (pintype "passive"))
    )
    (net (code "212") (name "unconnected-(U9-NC-Pad5)") (class "Default")
      (node (ref "U9") (pin "5") (pinfunction "NC_5") (pintype "passive"))
    )
  )
)
